# RoboDiscovery-F4_V1_0.net
KiCad netlist of a schematic drawn in EAGLE
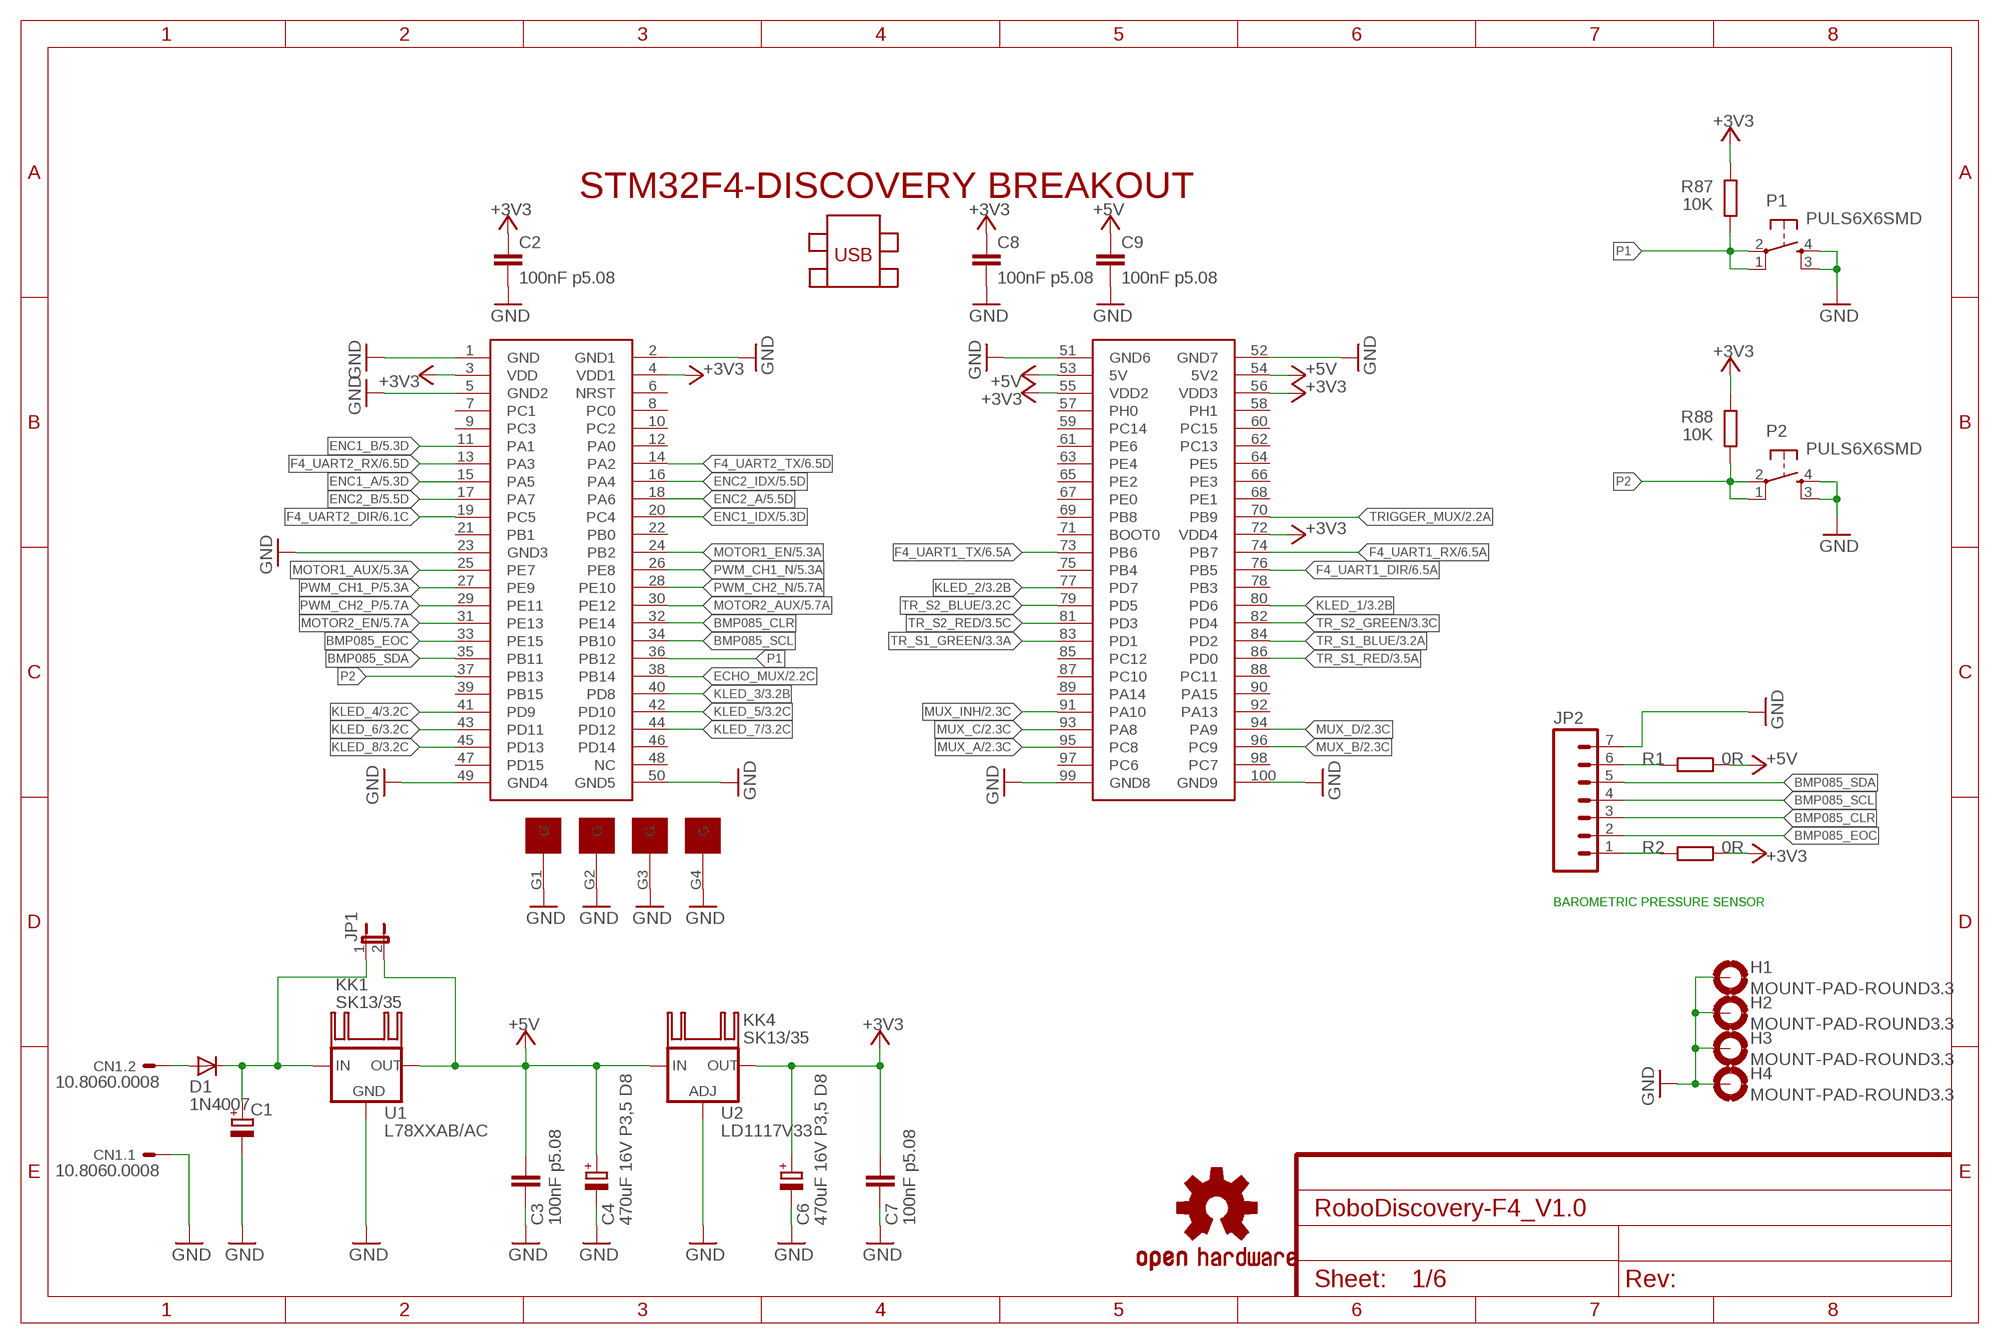
[diagram p0: schematic, sheet 1]
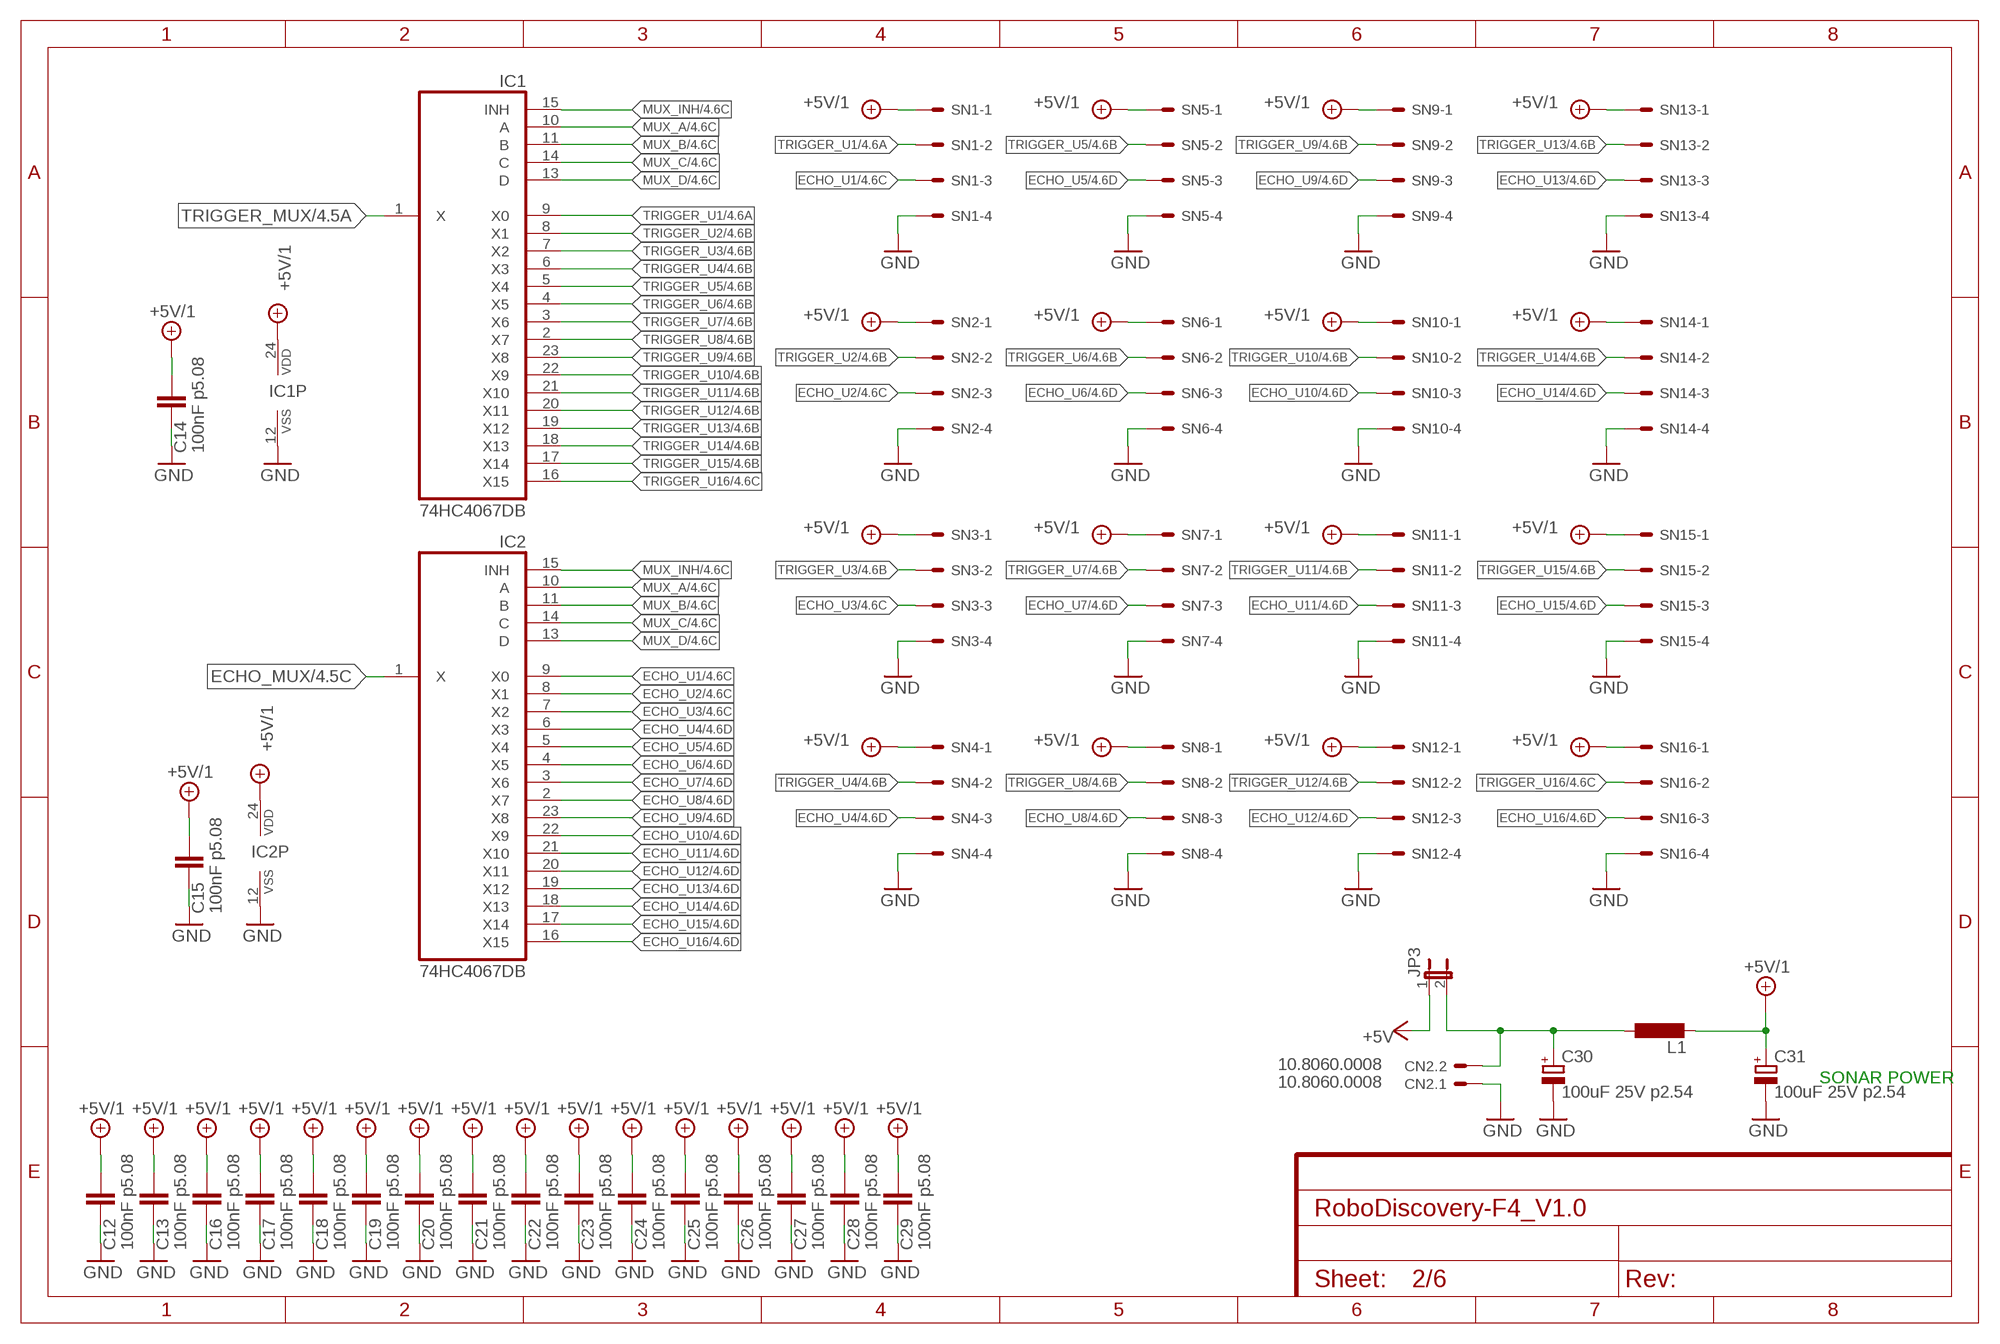
[diagram p1: schematic, sheet 2]
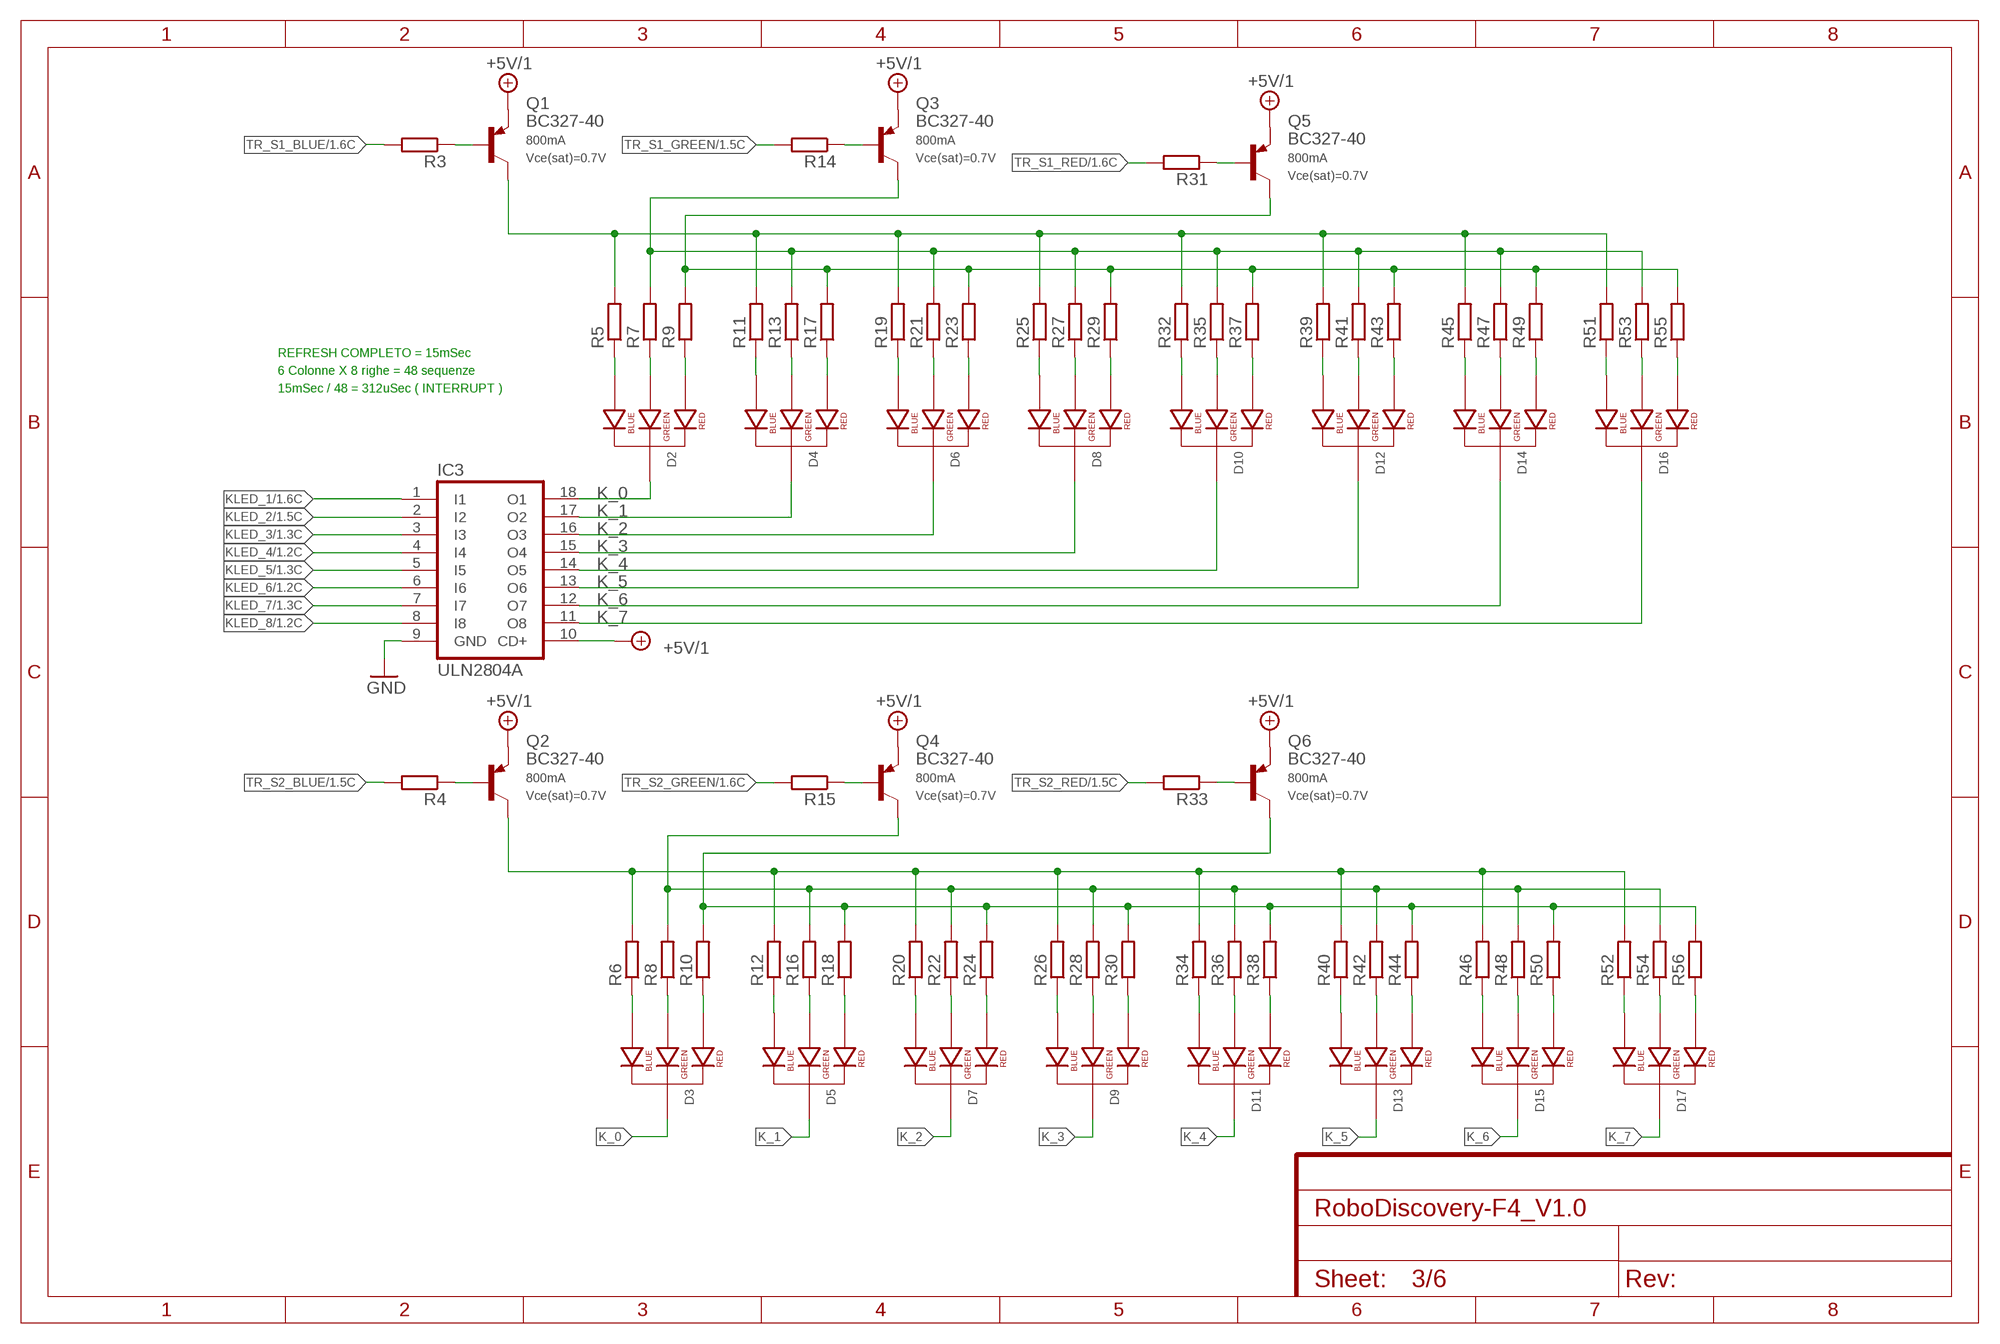
[diagram p2: schematic, sheet 3]
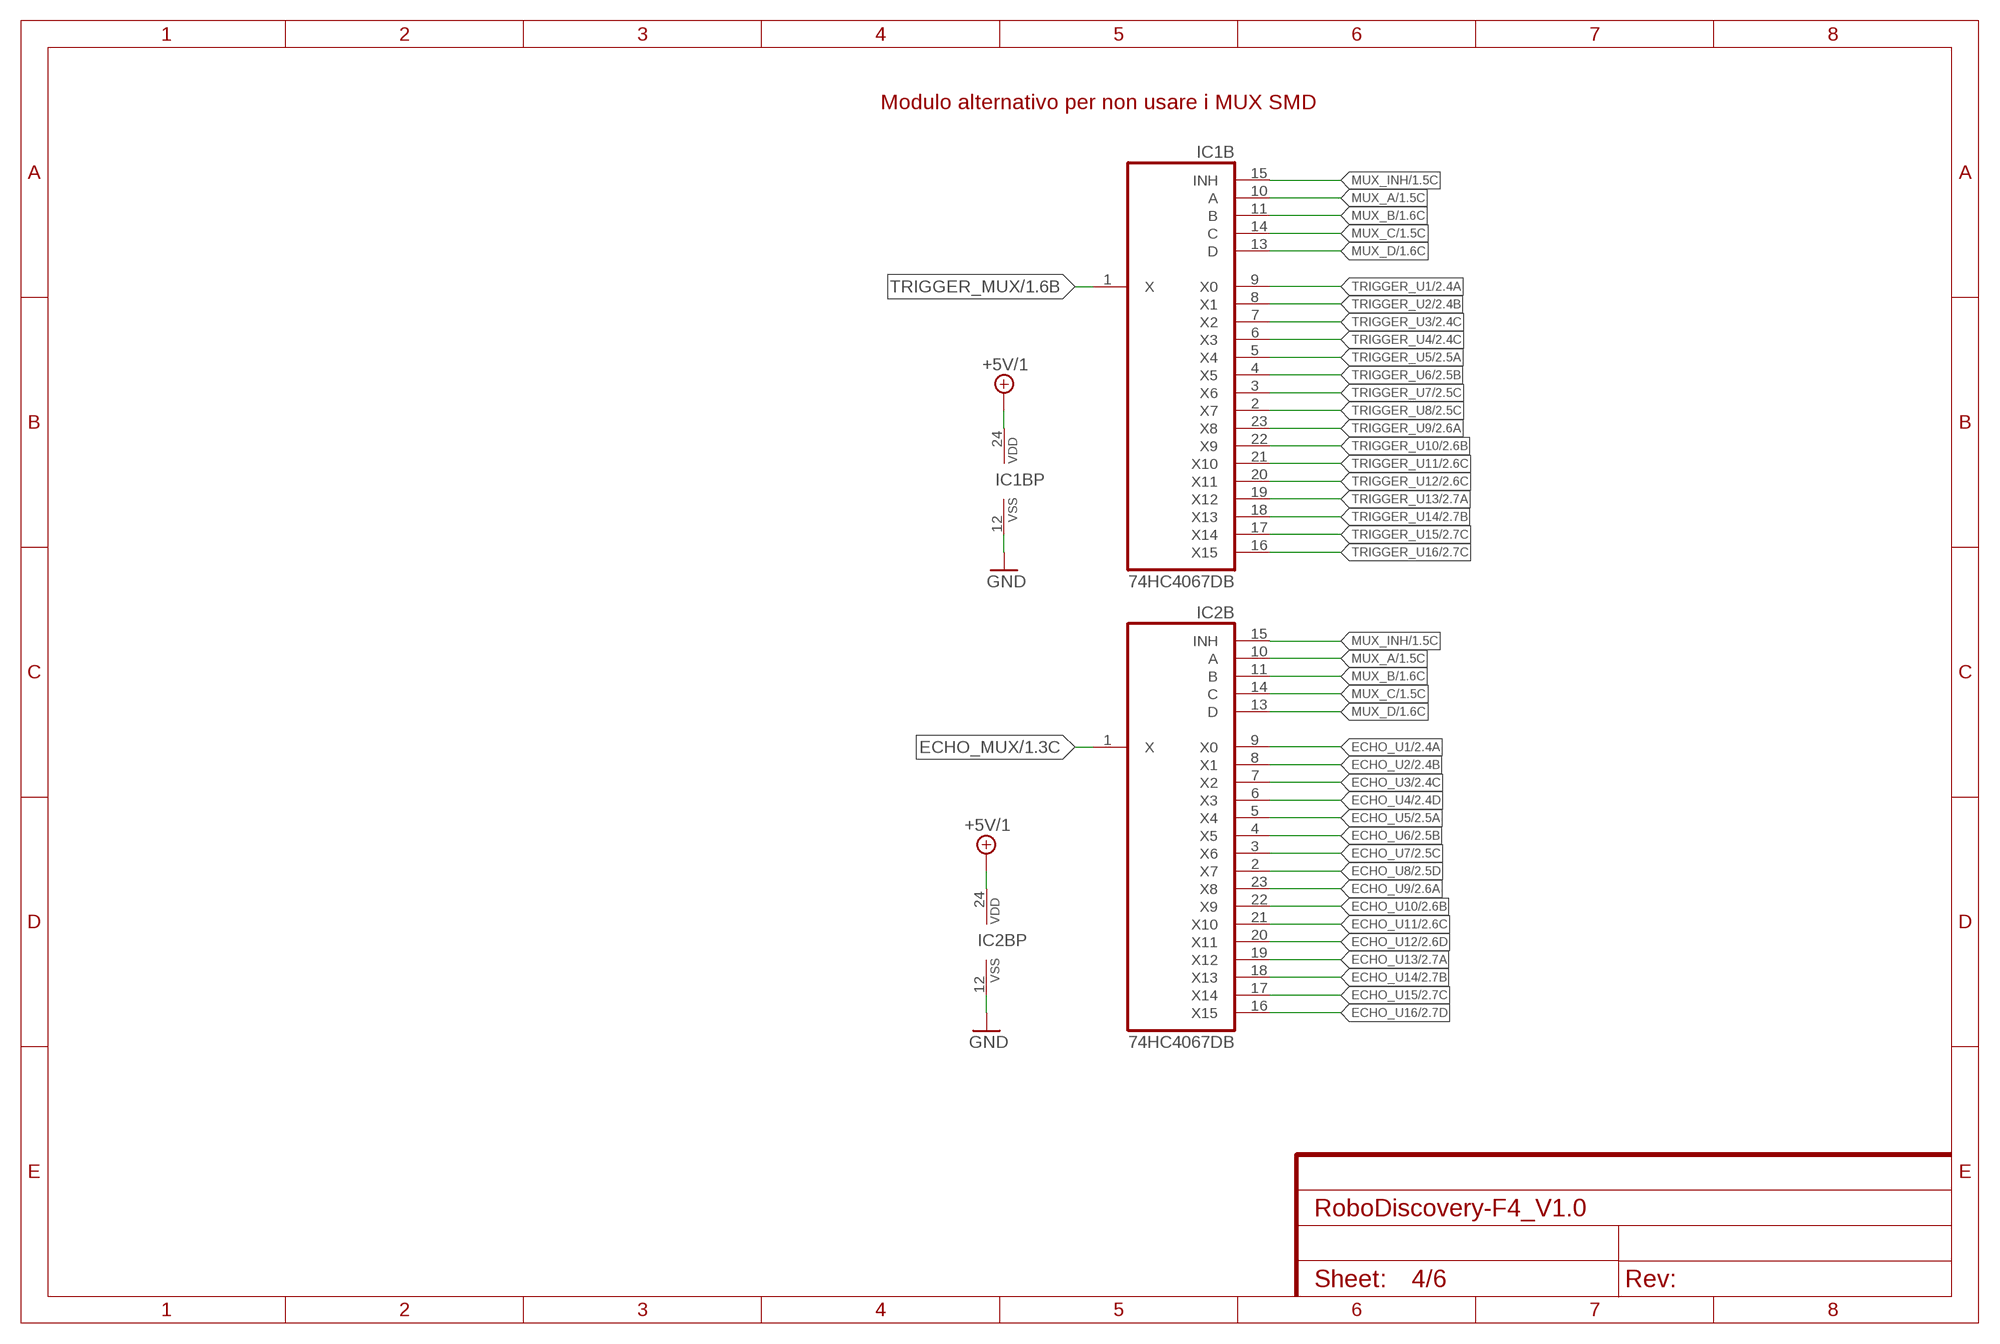
[diagram p3: schematic, sheet 4]
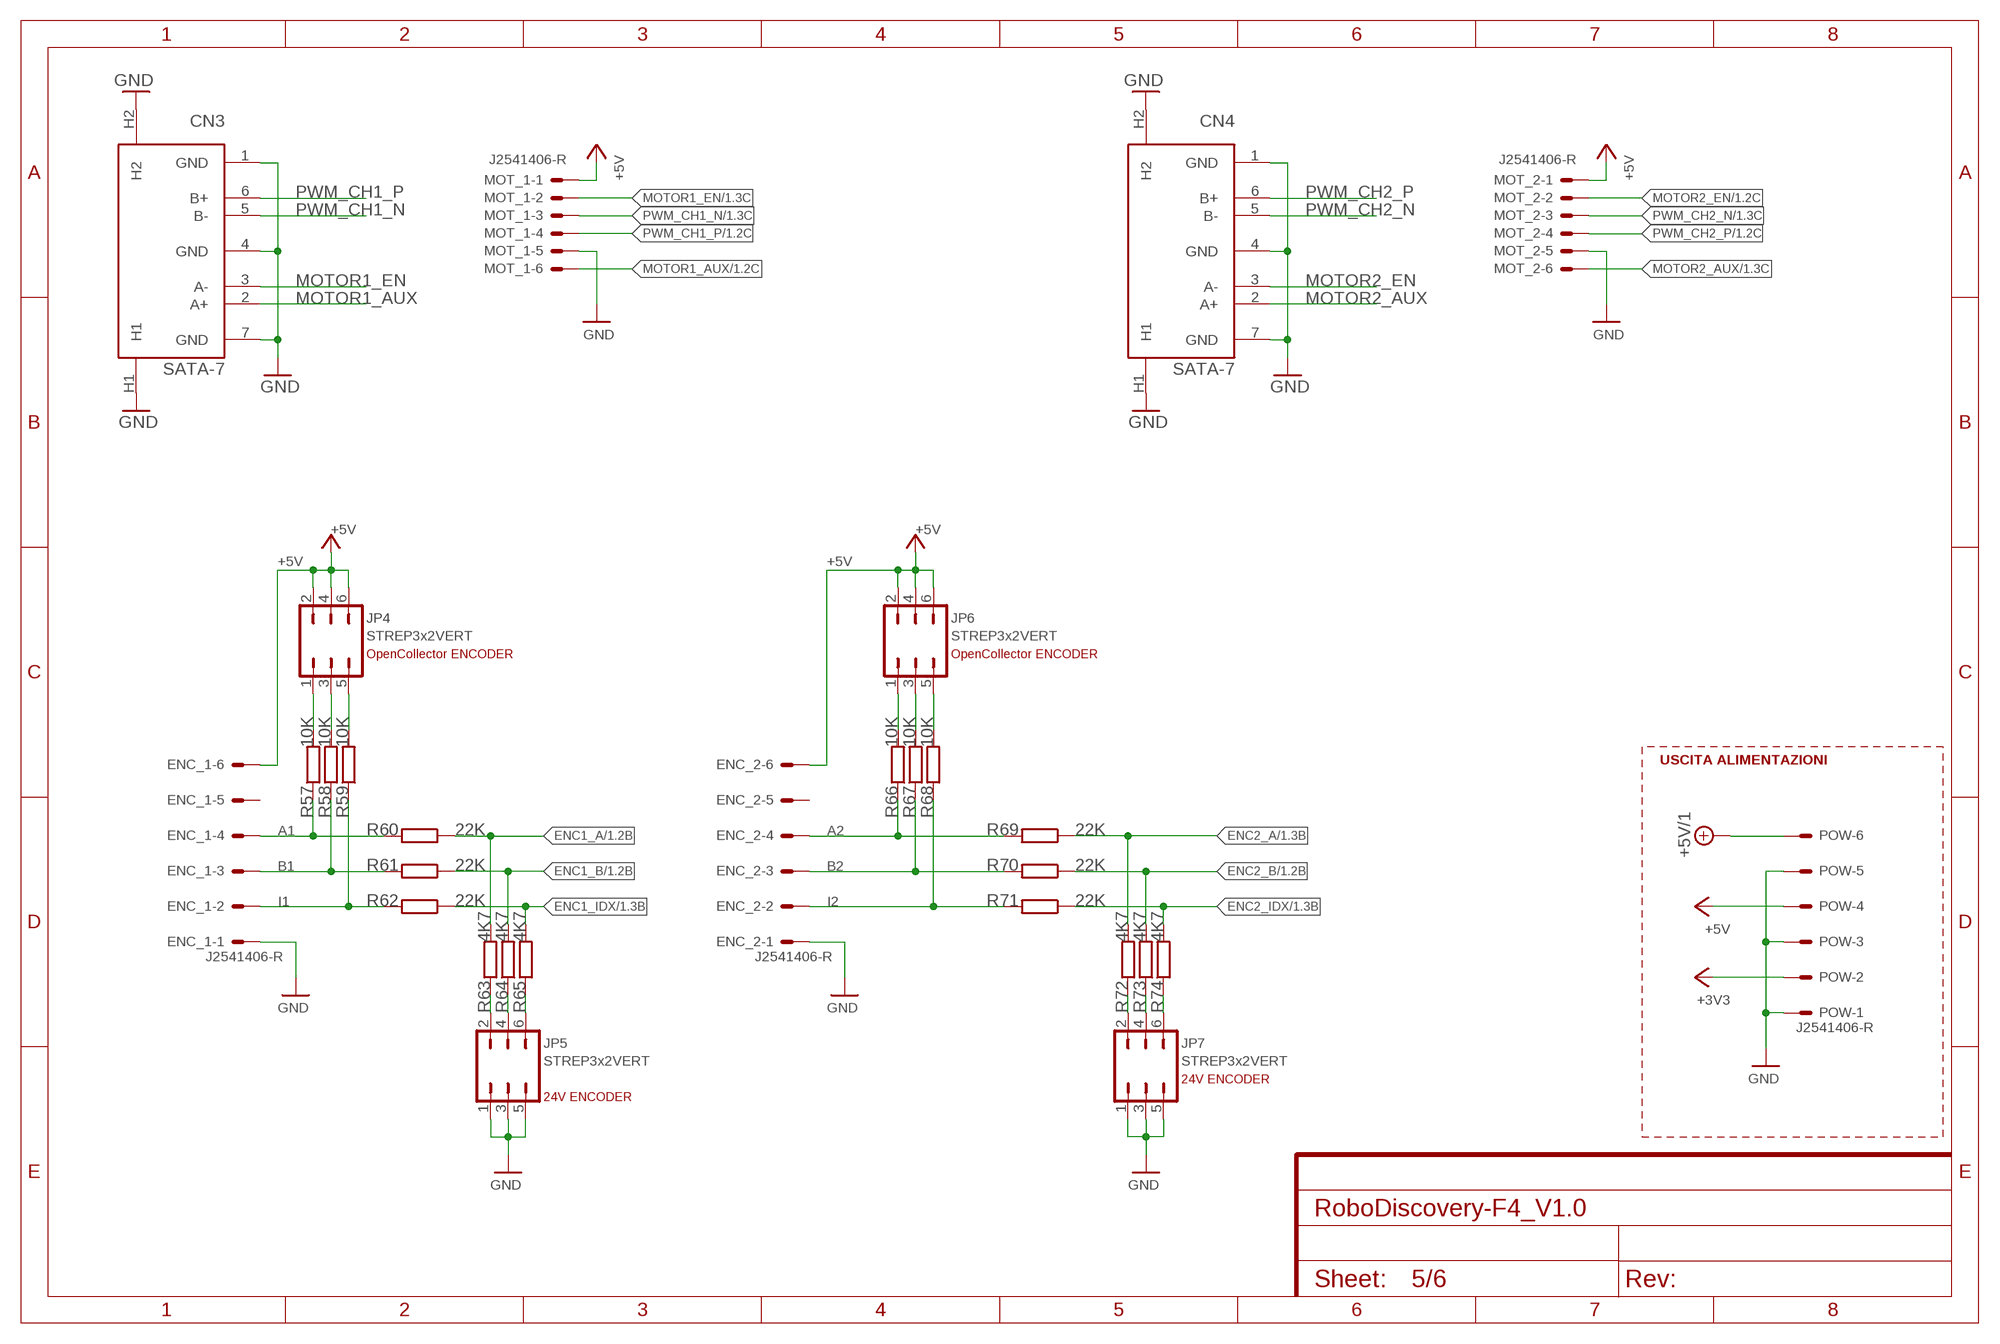
[diagram p4: schematic, sheet 5]
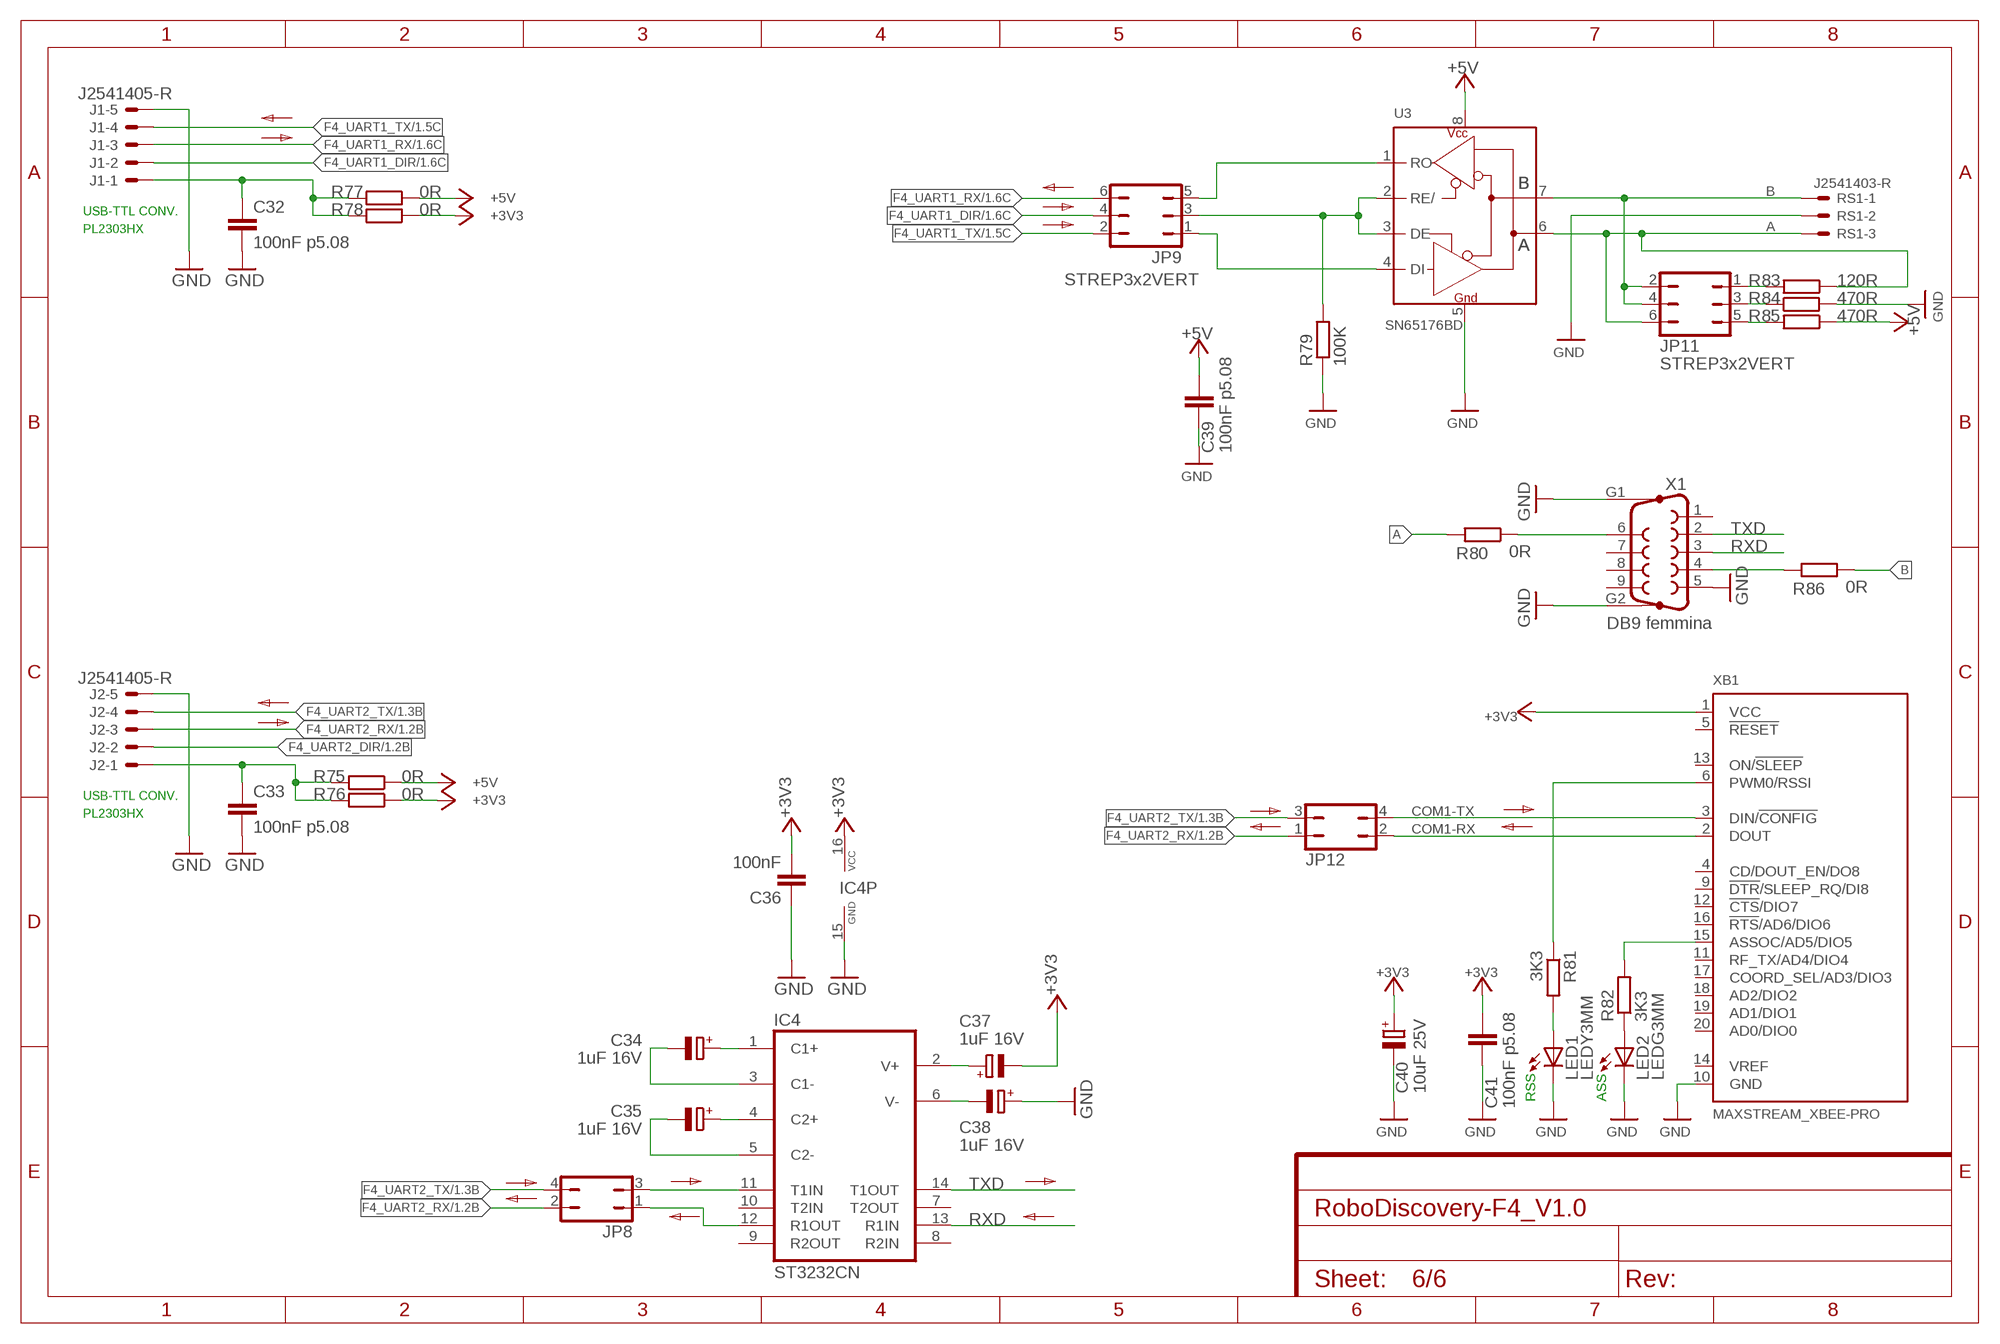
[diagram p5: schematic, sheet 6]

(export (version "E")
  (design (tool "Eeschema 10.0.6"))
  (components
    (comp (ref "D2")
      (value "LED-RGB-CC-THRUDIFFUSE")
      (footprint "eagle-import:LED-RGB-THRU")
      (libsource (lib "eagle-import") (part "LED-RGB-CC-THRUDIFFUSE"))
    )
    (comp (ref "D3")
      (value "LED-RGB-CC-THRUDIFFUSE")
      (footprint "eagle-import:LED-RGB-THRU")
      (libsource (lib "eagle-import") (part "LED-RGB-CC-THRUDIFFUSE"))
    )
    (comp (ref "D4")
      (value "LED-RGB-CC-THRUDIFFUSE")
      (footprint "eagle-import:LED-RGB-THRU")
      (libsource (lib "eagle-import") (part "LED-RGB-CC-THRUDIFFUSE"))
    )
    (comp (ref "D5")
      (value "LED-RGB-CC-THRUDIFFUSE")
      (footprint "eagle-import:LED-RGB-THRU")
      (libsource (lib "eagle-import") (part "LED-RGB-CC-THRUDIFFUSE"))
    )
    (comp (ref "D6")
      (value "LED-RGB-CC-THRUDIFFUSE")
      (footprint "eagle-import:LED-RGB-THRU")
      (libsource (lib "eagle-import") (part "LED-RGB-CC-THRUDIFFUSE"))
    )
    (comp (ref "D7")
      (value "LED-RGB-CC-THRUDIFFUSE")
      (footprint "eagle-import:LED-RGB-THRU")
      (libsource (lib "eagle-import") (part "LED-RGB-CC-THRUDIFFUSE"))
    )
    (comp (ref "D8")
      (value "LED-RGB-CC-THRUDIFFUSE")
      (footprint "eagle-import:LED-RGB-THRU")
      (libsource (lib "eagle-import") (part "LED-RGB-CC-THRUDIFFUSE"))
    )
    (comp (ref "D9")
      (value "LED-RGB-CC-THRUDIFFUSE")
      (footprint "eagle-import:LED-RGB-THRU")
      (libsource (lib "eagle-import") (part "LED-RGB-CC-THRUDIFFUSE"))
    )
    (comp (ref "D10")
      (value "LED-RGB-CC-THRUDIFFUSE")
      (footprint "eagle-import:LED-RGB-THRU")
      (libsource (lib "eagle-import") (part "LED-RGB-CC-THRUDIFFUSE"))
    )
    (comp (ref "D11")
      (value "LED-RGB-CC-THRUDIFFUSE")
      (footprint "eagle-import:LED-RGB-THRU")
      (libsource (lib "eagle-import") (part "LED-RGB-CC-THRUDIFFUSE"))
    )
    (comp (ref "D12")
      (value "LED-RGB-CC-THRUDIFFUSE")
      (footprint "eagle-import:LED-RGB-THRU")
      (libsource (lib "eagle-import") (part "LED-RGB-CC-THRUDIFFUSE"))
    )
    (comp (ref "D13")
      (value "LED-RGB-CC-THRUDIFFUSE")
      (footprint "eagle-import:LED-RGB-THRU")
      (libsource (lib "eagle-import") (part "LED-RGB-CC-THRUDIFFUSE"))
    )
    (comp (ref "D14")
      (value "LED-RGB-CC-THRUDIFFUSE")
      (footprint "eagle-import:LED-RGB-THRU")
      (libsource (lib "eagle-import") (part "LED-RGB-CC-THRUDIFFUSE"))
    )
    (comp (ref "D15")
      (value "LED-RGB-CC-THRUDIFFUSE")
      (footprint "eagle-import:LED-RGB-THRU")
      (libsource (lib "eagle-import") (part "LED-RGB-CC-THRUDIFFUSE"))
    )
    (comp (ref "D16")
      (value "LED-RGB-CC-THRUDIFFUSE")
      (footprint "eagle-import:LED-RGB-THRU")
      (libsource (lib "eagle-import") (part "LED-RGB-CC-THRUDIFFUSE"))
    )
    (comp (ref "D17")
      (value "LED-RGB-CC-THRUDIFFUSE")
      (footprint "eagle-import:LED-RGB-THRU")
      (libsource (lib "eagle-import") (part "LED-RGB-CC-THRUDIFFUSE"))
    )
    (comp (ref "IC3")
      (value "ULN2804A")
      (footprint "eagle-import:DIL18")
      (libsource (lib "eagle-import") (part "ULN2804A"))
    )
    (comp (ref "Q1")
      (value "BC327-40")
      (footprint "eagle-import:TO92-EBC")
      (fields (field (name "I") "800mA") (field (name "VCESAT") "Vce(sat)=0.7V"))
      (libsource (lib "eagle-import") (part "BC327-40"))
    )
    (comp (ref "Q2")
      (value "BC327-40")
      (footprint "eagle-import:TO92-EBC")
      (fields (field (name "I") "800mA") (field (name "VCESAT") "Vce(sat)=0.7V"))
      (libsource (lib "eagle-import") (part "BC327-40"))
    )
    (comp (ref "Q3")
      (value "BC327-40")
      (footprint "eagle-import:TO92-EBC")
      (fields (field (name "I") "800mA") (field (name "VCESAT") "Vce(sat)=0.7V"))
      (libsource (lib "eagle-import") (part "BC327-40"))
    )
    (comp (ref "Q4")
      (value "BC327-40")
      (footprint "eagle-import:TO92-EBC")
      (fields (field (name "I") "800mA") (field (name "VCESAT") "Vce(sat)=0.7V"))
      (libsource (lib "eagle-import") (part "BC327-40"))
    )
    (comp (ref "Q5")
      (value "BC327-40")
      (footprint "eagle-import:TO92-EBC")
      (fields (field (name "I") "800mA") (field (name "VCESAT") "Vce(sat)=0.7V"))
      (libsource (lib "eagle-import") (part "BC327-40"))
    )
    (comp (ref "Q6")
      (value "BC327-40")
      (footprint "eagle-import:TO92-EBC")
      (fields (field (name "I") "800mA") (field (name "VCESAT") "Vce(sat)=0.7V"))
      (libsource (lib "eagle-import") (part "BC327-40"))
    )
    (comp (ref "R3")
      (value "R-EU_0207/7")
      (footprint "eagle-import:0207_7")
      (libsource (lib "eagle-import") (part "R-EU_0207/7"))
    )
    (comp (ref "R4")
      (value "R-EU_0207/7")
      (footprint "eagle-import:0207_7")
      (libsource (lib "eagle-import") (part "R-EU_0207/7"))
    )
    (comp (ref "R5")
      (value "R-EU_0207/7")
      (footprint "eagle-import:0207_7")
      (libsource (lib "eagle-import") (part "R-EU_0207/7"))
    )
    (comp (ref "R6")
      (value "R-EU_0207/7")
      (footprint "eagle-import:0207_7")
      (libsource (lib "eagle-import") (part "R-EU_0207/7"))
    )
    (comp (ref "R7")
      (value "R-EU_0207/7")
      (footprint "eagle-import:0207_7")
      (libsource (lib "eagle-import") (part "R-EU_0207/7"))
    )
    (comp (ref "R8")
      (value "R-EU_0207/7")
      (footprint "eagle-import:0207_7")
      (libsource (lib "eagle-import") (part "R-EU_0207/7"))
    )
    (comp (ref "R9")
      (value "R-EU_0207/7")
      (footprint "eagle-import:0207_7")
      (libsource (lib "eagle-import") (part "R-EU_0207/7"))
    )
    (comp (ref "R10")
      (value "R-EU_0207/7")
      (footprint "eagle-import:0207_7")
      (libsource (lib "eagle-import") (part "R-EU_0207/7"))
    )
    (comp (ref "R11")
      (value "R-EU_0207/7")
      (footprint "eagle-import:0207_7")
      (libsource (lib "eagle-import") (part "R-EU_0207/7"))
    )
    (comp (ref "R12")
      (value "R-EU_0207/7")
      (footprint "eagle-import:0207_7")
      (libsource (lib "eagle-import") (part "R-EU_0207/7"))
    )
    (comp (ref "R13")
      (value "R-EU_0207/7")
      (footprint "eagle-import:0207_7")
      (libsource (lib "eagle-import") (part "R-EU_0207/7"))
    )
    (comp (ref "R14")
      (value "R-EU_0207/7")
      (footprint "eagle-import:0207_7")
      (libsource (lib "eagle-import") (part "R-EU_0207/7"))
    )
    (comp (ref "R15")
      (value "R-EU_0207/7")
      (footprint "eagle-import:0207_7")
      (libsource (lib "eagle-import") (part "R-EU_0207/7"))
    )
    (comp (ref "R16")
      (value "R-EU_0207/7")
      (footprint "eagle-import:0207_7")
      (libsource (lib "eagle-import") (part "R-EU_0207/7"))
    )
    (comp (ref "R17")
      (value "R-EU_0207/7")
      (footprint "eagle-import:0207_7")
      (libsource (lib "eagle-import") (part "R-EU_0207/7"))
    )
    (comp (ref "R18")
      (value "R-EU_0207/7")
      (footprint "eagle-import:0207_7")
      (libsource (lib "eagle-import") (part "R-EU_0207/7"))
    )
    (comp (ref "R19")
      (value "R-EU_0207/7")
      (footprint "eagle-import:0207_7")
      (libsource (lib "eagle-import") (part "R-EU_0207/7"))
    )
    (comp (ref "R20")
      (value "R-EU_0207/7")
      (footprint "eagle-import:0207_7")
      (libsource (lib "eagle-import") (part "R-EU_0207/7"))
    )
    (comp (ref "R21")
      (value "R-EU_0207/7")
      (footprint "eagle-import:0207_7")
      (libsource (lib "eagle-import") (part "R-EU_0207/7"))
    )
    (comp (ref "R22")
      (value "R-EU_0207/7")
      (footprint "eagle-import:0207_7")
      (libsource (lib "eagle-import") (part "R-EU_0207/7"))
    )
    (comp (ref "R23")
      (value "R-EU_0207/7")
      (footprint "eagle-import:0207_7")
      (libsource (lib "eagle-import") (part "R-EU_0207/7"))
    )
    (comp (ref "R24")
      (value "R-EU_0207/7")
      (footprint "eagle-import:0207_7")
      (libsource (lib "eagle-import") (part "R-EU_0207/7"))
    )
    (comp (ref "R25")
      (value "R-EU_0207/7")
      (footprint "eagle-import:0207_7")
      (libsource (lib "eagle-import") (part "R-EU_0207/7"))
    )
    (comp (ref "R26")
      (value "R-EU_0207/7")
      (footprint "eagle-import:0207_7")
      (libsource (lib "eagle-import") (part "R-EU_0207/7"))
    )
    (comp (ref "R27")
      (value "R-EU_0207/7")
      (footprint "eagle-import:0207_7")
      (libsource (lib "eagle-import") (part "R-EU_0207/7"))
    )
    (comp (ref "R28")
      (value "R-EU_0207/7")
      (footprint "eagle-import:0207_7")
      (libsource (lib "eagle-import") (part "R-EU_0207/7"))
    )
    (comp (ref "R29")
      (value "R-EU_0207/7")
      (footprint "eagle-import:0207_7")
      (libsource (lib "eagle-import") (part "R-EU_0207/7"))
    )
    (comp (ref "R30")
      (value "R-EU_0207/7")
      (footprint "eagle-import:0207_7")
      (libsource (lib "eagle-import") (part "R-EU_0207/7"))
    )
    (comp (ref "R31")
      (value "R-EU_0207/7")
      (footprint "eagle-import:0207_7")
      (libsource (lib "eagle-import") (part "R-EU_0207/7"))
    )
    (comp (ref "R32")
      (value "R-EU_0207/7")
      (footprint "eagle-import:0207_7")
      (libsource (lib "eagle-import") (part "R-EU_0207/7"))
    )
    (comp (ref "R33")
      (value "R-EU_0207/7")
      (footprint "eagle-import:0207_7")
      (libsource (lib "eagle-import") (part "R-EU_0207/7"))
    )
    (comp (ref "R34")
      (value "R-EU_0207/7")
      (footprint "eagle-import:0207_7")
      (libsource (lib "eagle-import") (part "R-EU_0207/7"))
    )
    (comp (ref "R35")
      (value "R-EU_0207/7")
      (footprint "eagle-import:0207_7")
      (libsource (lib "eagle-import") (part "R-EU_0207/7"))
    )
    (comp (ref "R36")
      (value "R-EU_0207/7")
      (footprint "eagle-import:0207_7")
      (libsource (lib "eagle-import") (part "R-EU_0207/7"))
    )
    (comp (ref "R37")
      (value "R-EU_0207/7")
      (footprint "eagle-import:0207_7")
      (libsource (lib "eagle-import") (part "R-EU_0207/7"))
    )
    (comp (ref "R38")
      (value "R-EU_0207/7")
      (footprint "eagle-import:0207_7")
      (libsource (lib "eagle-import") (part "R-EU_0207/7"))
    )
    (comp (ref "R39")
      (value "R-EU_0207/7")
      (footprint "eagle-import:0207_7")
      (libsource (lib "eagle-import") (part "R-EU_0207/7"))
    )
    (comp (ref "R40")
      (value "R-EU_0207/7")
      (footprint "eagle-import:0207_7")
      (libsource (lib "eagle-import") (part "R-EU_0207/7"))
    )
    (comp (ref "R41")
      (value "R-EU_0207/7")
      (footprint "eagle-import:0207_7")
      (libsource (lib "eagle-import") (part "R-EU_0207/7"))
    )
    (comp (ref "R42")
      (value "R-EU_0207/7")
      (footprint "eagle-import:0207_7")
      (libsource (lib "eagle-import") (part "R-EU_0207/7"))
    )
    (comp (ref "R43")
      (value "R-EU_0207/7")
      (footprint "eagle-import:0207_7")
      (libsource (lib "eagle-import") (part "R-EU_0207/7"))
    )
    (comp (ref "R44")
      (value "R-EU_0207/7")
      (footprint "eagle-import:0207_7")
      (libsource (lib "eagle-import") (part "R-EU_0207/7"))
    )
    (comp (ref "R45")
      (value "R-EU_0207/7")
      (footprint "eagle-import:0207_7")
      (libsource (lib "eagle-import") (part "R-EU_0207/7"))
    )
    (comp (ref "R46")
      (value "R-EU_0207/7")
      (footprint "eagle-import:0207_7")
      (libsource (lib "eagle-import") (part "R-EU_0207/7"))
    )
    (comp (ref "R47")
      (value "R-EU_0207/7")
      (footprint "eagle-import:0207_7")
      (libsource (lib "eagle-import") (part "R-EU_0207/7"))
    )
    (comp (ref "R48")
      (value "R-EU_0207/7")
      (footprint "eagle-import:0207_7")
      (libsource (lib "eagle-import") (part "R-EU_0207/7"))
    )
    (comp (ref "R49")
      (value "R-EU_0207/7")
      (footprint "eagle-import:0207_7")
      (libsource (lib "eagle-import") (part "R-EU_0207/7"))
    )
    (comp (ref "R50")
      (value "R-EU_0207/7")
      (footprint "eagle-import:0207_7")
      (libsource (lib "eagle-import") (part "R-EU_0207/7"))
    )
    (comp (ref "R51")
      (value "R-EU_0207/7")
      (footprint "eagle-import:0207_7")
      (libsource (lib "eagle-import") (part "R-EU_0207/7"))
    )
    (comp (ref "R52")
      (value "R-EU_0207/7")
      (footprint "eagle-import:0207_7")
      (libsource (lib "eagle-import") (part "R-EU_0207/7"))
    )
    (comp (ref "R53")
      (value "R-EU_0207/7")
      (footprint "eagle-import:0207_7")
      (libsource (lib "eagle-import") (part "R-EU_0207/7"))
    )
    (comp (ref "R54")
      (value "R-EU_0207/7")
      (footprint "eagle-import:0207_7")
      (libsource (lib "eagle-import") (part "R-EU_0207/7"))
    )
    (comp (ref "R55")
      (value "R-EU_0207/7")
      (footprint "eagle-import:0207_7")
      (libsource (lib "eagle-import") (part "R-EU_0207/7"))
    )
    (comp (ref "R56")
      (value "R-EU_0207/7")
      (footprint "eagle-import:0207_7")
      (libsource (lib "eagle-import") (part "R-EU_0207/7"))
    )
    (comp (ref "C12")
      (value "100nF p5.08")
      (footprint "eagle-import:C050-024X044")
      (libsource (lib "eagle-import") (part "C-EU050-024X044"))
    )
    (comp (ref "C13")
      (value "100nF p5.08")
      (footprint "eagle-import:C050-024X044")
      (libsource (lib "eagle-import") (part "C-EU050-024X044"))
    )
    (comp (ref "C14")
      (value "100nF p5.08")
      (footprint "eagle-import:C050-024X044")
      (libsource (lib "eagle-import") (part "C-EU050-024X044"))
    )
    (comp (ref "C15")
      (value "100nF p5.08")
      (footprint "eagle-import:C050-024X044")
      (libsource (lib "eagle-import") (part "C-EU050-024X044"))
    )
    (comp (ref "C16")
      (value "100nF p5.08")
      (footprint "eagle-import:C050-024X044")
      (libsource (lib "eagle-import") (part "C-EU050-024X044"))
    )
    (comp (ref "C17")
      (value "100nF p5.08")
      (footprint "eagle-import:C050-024X044")
      (libsource (lib "eagle-import") (part "C-EU050-024X044"))
    )
    (comp (ref "C18")
      (value "100nF p5.08")
      (footprint "eagle-import:C050-024X044")
      (libsource (lib "eagle-import") (part "C-EU050-024X044"))
    )
    (comp (ref "C19")
      (value "100nF p5.08")
      (footprint "eagle-import:C050-024X044")
      (libsource (lib "eagle-import") (part "C-EU050-024X044"))
    )
    (comp (ref "C20")
      (value "100nF p5.08")
      (footprint "eagle-import:C050-024X044")
      (libsource (lib "eagle-import") (part "C-EU050-024X044"))
    )
    (comp (ref "C21")
      (value "100nF p5.08")
      (footprint "eagle-import:C050-024X044")
      (libsource (lib "eagle-import") (part "C-EU050-024X044"))
    )
    (comp (ref "C22")
      (value "100nF p5.08")
      (footprint "eagle-import:C050-024X044")
      (libsource (lib "eagle-import") (part "C-EU050-024X044"))
    )
    (comp (ref "C23")
      (value "100nF p5.08")
      (footprint "eagle-import:C050-024X044")
      (libsource (lib "eagle-import") (part "C-EU050-024X044"))
    )
    (comp (ref "C24")
      (value "100nF p5.08")
      (footprint "eagle-import:C050-024X044")
      (libsource (lib "eagle-import") (part "C-EU050-024X044"))
    )
    (comp (ref "C25")
      (value "100nF p5.08")
      (footprint "eagle-import:C050-024X044")
      (libsource (lib "eagle-import") (part "C-EU050-024X044"))
    )
    (comp (ref "C26")
      (value "100nF p5.08")
      (footprint "eagle-import:C050-024X044")
      (libsource (lib "eagle-import") (part "C-EU050-024X044"))
    )
    (comp (ref "C27")
      (value "100nF p5.08")
      (footprint "eagle-import:C050-024X044")
      (libsource (lib "eagle-import") (part "C-EU050-024X044"))
    )
    (comp (ref "C28")
      (value "100nF p5.08")
      (footprint "eagle-import:C050-024X044")
      (libsource (lib "eagle-import") (part "C-EU050-024X044"))
    )
    (comp (ref "C29")
      (value "100nF p5.08")
      (footprint "eagle-import:C050-024X044")
      (libsource (lib "eagle-import") (part "C-EU050-024X044"))
    )
    (comp (ref "C30")
      (value "100uF 25V p2.54")
      (footprint "eagle-import:E2,5-6")
      (libsource (lib "eagle-import") (part "CPOL-EUE2.5-6"))
    )
    (comp (ref "C31")
      (value "100uF 25V p2.54")
      (footprint "eagle-import:E2,5-6")
      (libsource (lib "eagle-import") (part "CPOL-EUE2.5-6"))
    )
    (comp (ref "CN2")
      (value "10.8060.0008")
      (footprint "eagle-import:300-021-13_2P_5VE")
      (libsource (lib "eagle-import") (part "10.8060.0008"))
    )
    (comp (ref "IC1")
      (value "74HC4067DB")
      (footprint "eagle-import:SO24W")
      (libsource (lib "eagle-import") (part "4067D"))
    )
    (comp (ref "IC2")
      (value "74HC4067DB")
      (footprint "eagle-import:SO24W")
      (libsource (lib "eagle-import") (part "4067D"))
    )
    (comp (ref "JP3")
      (value "JP1E")
      (footprint "eagle-import:JP1")
      (libsource (lib "eagle-import") (part "JP1E"))
    )
    (comp (ref "L1")
      (value "L-EU2200-12.7")
      (footprint "eagle-import:2200-12.7")
      (libsource (lib "eagle-import") (part "L-EU2200-12.7"))
    )
    (comp (ref "SN1")
      (value "22-27-2041-04")
      (footprint "eagle-import:6410-04")
      (libsource (lib "eagle-import") (part "22-?-0427-2041"))
    )
    (comp (ref "SN2")
      (value "22-27-2041-04")
      (footprint "eagle-import:6410-04")
      (libsource (lib "eagle-import") (part "22-?-0427-2041"))
    )
    (comp (ref "SN3")
      (value "22-27-2041-04")
      (footprint "eagle-import:6410-04")
      (libsource (lib "eagle-import") (part "22-?-0427-2041"))
    )
    (comp (ref "SN4")
      (value "22-27-2041-04")
      (footprint "eagle-import:6410-04")
      (libsource (lib "eagle-import") (part "22-?-0427-2041"))
    )
    (comp (ref "SN5")
      (value "22-27-2041-04")
      (footprint "eagle-import:6410-04")
      (libsource (lib "eagle-import") (part "22-?-0427-2041"))
    )
    (comp (ref "SN6")
      (value "22-27-2041-04")
      (footprint "eagle-import:6410-04")
      (libsource (lib "eagle-import") (part "22-?-0427-2041"))
    )
    (comp (ref "SN7")
      (value "22-27-2041-04")
      (footprint "eagle-import:6410-04")
      (libsource (lib "eagle-import") (part "22-?-0427-2041"))
    )
    (comp (ref "SN8")
      (value "22-27-2041-04")
      (footprint "eagle-import:6410-04")
      (libsource (lib "eagle-import") (part "22-?-0427-2041"))
    )
    (comp (ref "SN9")
      (value "22-27-2041-04")
      (footprint "eagle-import:6410-04")
      (libsource (lib "eagle-import") (part "22-?-0427-2041"))
    )
    (comp (ref "SN10")
      (value "22-27-2041-04")
      (footprint "eagle-import:6410-04")
      (libsource (lib "eagle-import") (part "22-?-0427-2041"))
    )
    (comp (ref "SN11")
      (value "22-27-2041-04")
      (footprint "eagle-import:6410-04")
      (libsource (lib "eagle-import") (part "22-?-0427-2041"))
    )
    (comp (ref "SN12")
      (value "22-27-2041-04")
      (footprint "eagle-import:6410-04")
      (libsource (lib "eagle-import") (part "22-?-0427-2041"))
    )
    (comp (ref "SN13")
      (value "22-27-2041-04")
      (footprint "eagle-import:6410-04")
      (libsource (lib "eagle-import") (part "22-?-0427-2041"))
    )
    (comp (ref "SN14")
      (value "22-27-2041-04")
      (footprint "eagle-import:6410-04")
      (libsource (lib "eagle-import") (part "22-?-0427-2041"))
    )
    (comp (ref "SN15")
      (value "22-27-2041-04")
      (footprint "eagle-import:6410-04")
      (libsource (lib "eagle-import") (part "22-?-0427-2041"))
    )
    (comp (ref "SN16")
      (value "22-27-2041-04")
      (footprint "eagle-import:6410-04")
      (libsource (lib "eagle-import") (part "22-?-0427-2041"))
    )
    (comp (ref "C32")
      (value "100nF p5.08")
      (footprint "eagle-import:C050-024X044")
      (libsource (lib "eagle-import") (part "C-EU050-024X044"))
    )
    (comp (ref "C33")
      (value "100nF p5.08")
      (footprint "eagle-import:C050-024X044")
      (libsource (lib "eagle-import") (part "C-EU050-024X044"))
    )
    (comp (ref "C34")
      (value "1uF 16V")
      (footprint "eagle-import:E2,5-5")
      (libsource (lib "eagle-import") (part "CPOL-EUE2.5-5"))
    )
    (comp (ref "C35")
      (value "1uF 16V")
      (footprint "eagle-import:E2,5-5")
      (libsource (lib "eagle-import") (part "CPOL-EUE2.5-5"))
    )
    (comp (ref "C36")
      (value "100nF")
      (footprint "eagle-import:C025-025X050")
      (libsource (lib "eagle-import") (part "C-EU025-025X050"))
    )
    (comp (ref "C37")
      (value "1uF 16V")
      (footprint "eagle-import:E2,5-5")
      (libsource (lib "eagle-import") (part "CPOL-EUE2.5-5"))
    )
    (comp (ref "C38")
      (value "1uF 16V")
      (footprint "eagle-import:E2,5-5")
      (libsource (lib "eagle-import") (part "CPOL-EUE2.5-5"))
    )
    (comp (ref "C39")
      (value "100nF p5.08")
      (footprint "eagle-import:C050-024X044")
      (libsource (lib "eagle-import") (part "C-EU050-024X044"))
    )
    (comp (ref "C40")
      (value "10uF 25V")
      (footprint "eagle-import:E2,5-5")
      (libsource (lib "eagle-import") (part "CPOL-EUE2.5-5"))
    )
    (comp (ref "C41")
      (value "100nF p5.08")
      (footprint "eagle-import:C050-024X044")
      (libsource (lib "eagle-import") (part "C-EU050-024X044"))
    )
    (comp (ref "IC4")
      (value "ST3232CN")
      (footprint "eagle-import:DIL16")
      (fields (field (name "MF") "MAXIM") (field (name "MPN") "MAX232ACPE+"))
      (libsource (lib "eagle-import") (part "MAX232"))
    )
    (comp (ref "J1")
      (value "J2541405-R")
      (footprint "eagle-import:6410-05")
      (libsource (lib "eagle-import") (part "22-?-0527-2051"))
    )
    (comp (ref "J2")
      (value "J2541405-R")
      (footprint "eagle-import:6410-05")
      (libsource (lib "eagle-import") (part "22-?-0527-2051"))
    )
    (comp (ref "JP8")
      (value "JP2Q")
      (footprint "eagle-import:JP2Q")
      (libsource (lib "eagle-import") (part "JP2Q"))
    )
    (comp (ref "JP9")
      (value "STREP3x2VERT")
      (footprint "eagle-import:JP3Q")
      (libsource (lib "eagle-import") (part "JP3Q"))
    )
    (comp (ref "JP11")
      (value "STREP3x2VERT")
      (footprint "eagle-import:JP3Q")
      (libsource (lib "eagle-import") (part "JP3Q"))
    )
    (comp (ref "JP12")
      (value "JP2Q")
      (footprint "eagle-import:JP2Q")
      (libsource (lib "eagle-import") (part "JP2Q"))
    )
    (comp (ref "LED1")
      (value "LEDY3MM")
      (footprint "eagle-import:LED3MM")
      (libsource (lib "eagle-import") (part "LED3MM"))
    )
    (comp (ref "LED2")
      (value "LEDG3MM")
      (footprint "eagle-import:LED3MM")
      (libsource (lib "eagle-import") (part "LED3MM"))
    )
    (comp (ref "R75")
      (value "0R")
      (footprint "eagle-import:0207_7")
      (libsource (lib "eagle-import") (part "R-EU_0207/7"))
    )
    (comp (ref "R76")
      (value "0R")
      (footprint "eagle-import:0207_7")
      (libsource (lib "eagle-import") (part "R-EU_0207/7"))
    )
    (comp (ref "R77")
      (value "0R")
      (footprint "eagle-import:0207_7")
      (libsource (lib "eagle-import") (part "R-EU_0207/7"))
    )
    (comp (ref "R78")
      (value "0R")
      (footprint "eagle-import:0207_7")
      (libsource (lib "eagle-import") (part "R-EU_0207/7"))
    )
    (comp (ref "R79")
      (value "100K")
      (footprint "eagle-import:0207_7")
      (libsource (lib "eagle-import") (part "R-EU_0207/7"))
    )
    (comp (ref "R80")
      (value "0R")
      (footprint "eagle-import:0207_7")
      (libsource (lib "eagle-import") (part "R-EU_0207/7"))
    )
    (comp (ref "R81")
      (value "3K3")
      (footprint "eagle-import:0207_7")
      (libsource (lib "eagle-import") (part "R-EU_0207/7"))
    )
    (comp (ref "R82")
      (value "3K3")
      (footprint "eagle-import:0207_7")
      (libsource (lib "eagle-import") (part "R-EU_0207/7"))
    )
    (comp (ref "R83")
      (value "120R")
      (footprint "eagle-import:0207_7")
      (libsource (lib "eagle-import") (part "R-EU_0207/7"))
    )
    (comp (ref "R84")
      (value "470R")
      (footprint "eagle-import:0207_7")
      (libsource (lib "eagle-import") (part "R-EU_0207/7"))
    )
    (comp (ref "R85")
      (value "470R")
      (footprint "eagle-import:0207_7")
      (libsource (lib "eagle-import") (part "R-EU_0207/7"))
    )
    (comp (ref "R86")
      (value "0R")
      (footprint "eagle-import:0207_7")
      (libsource (lib "eagle-import") (part "R-EU_0207/7"))
    )
    (comp (ref "RS1")
      (value "J2541403-R")
      (footprint "eagle-import:6410-03")
      (libsource (lib "eagle-import") (part "22-?-0327-2031"))
    )
    (comp (ref "U3")
      (value "SN65176BD")
      (footprint "eagle-import:DIL8")
      (libsource (lib "eagle-import") (part "MAX485_DIP"))
    )
    (comp (ref "X1")
      (value "DB9 femmina")
      (footprint "eagle-import:F09HP")
      (libsource (lib "eagle-import") (part "F09HP"))
    )
    (comp (ref "XB1")
      (value "MAXSTREAM_XBEE-PRO")
      (footprint "eagle-import:MAXSTREAM_XBEE-PRO")
      (libsource (lib "eagle-import") (part "MAXSTREAM_XBEE-PRO"))
    )
    (comp (ref "IC1B")
      (value "74HC4067DB")
      (footprint "eagle-import:DIL24-6")
      (libsource (lib "eagle-import") (part "4067N"))
    )
    (comp (ref "IC2B")
      (value "74HC4067DB")
      (footprint "eagle-import:DIL24-6")
      (libsource (lib "eagle-import") (part "4067N"))
    )
    (comp (ref "CN3")
      (value "SATA-7")
      (footprint "eagle-import:SATA-5607-5102-SH")
      (libsource (lib "eagle-import") (part "SATA-7"))
    )
    (comp (ref "CN4")
      (value "SATA-7")
      (footprint "eagle-import:SATA-5607-5102-SH")
      (libsource (lib "eagle-import") (part "SATA-7"))
    )
    (comp (ref "ENC_1")
      (value "J2541406-R")
      (footprint "eagle-import:6410-06")
      (libsource (lib "eagle-import") (part "22-?-0627-2061"))
    )
    (comp (ref "ENC_2")
      (value "J2541406-R")
      (footprint "eagle-import:6410-06")
      (libsource (lib "eagle-import") (part "22-?-0627-2061"))
    )
    (comp (ref "JP4")
      (value "STREP3x2VERT")
      (footprint "eagle-import:JP3Q")
      (libsource (lib "eagle-import") (part "JP3Q"))
    )
    (comp (ref "JP5")
      (value "STREP3x2VERT")
      (footprint "eagle-import:JP3Q")
      (libsource (lib "eagle-import") (part "JP3Q"))
    )
    (comp (ref "JP6")
      (value "STREP3x2VERT")
      (footprint "eagle-import:JP3Q")
      (libsource (lib "eagle-import") (part "JP3Q"))
    )
    (comp (ref "JP7")
      (value "STREP3x2VERT")
      (footprint "eagle-import:JP3Q")
      (libsource (lib "eagle-import") (part "JP3Q"))
    )
    (comp (ref "MOT_1")
      (value "J2541406-R")
      (footprint "eagle-import:6410-06")
      (libsource (lib "eagle-import") (part "22-?-0627-2061"))
    )
    (comp (ref "MOT_2")
      (value "J2541406-R")
      (footprint "eagle-import:6410-06")
      (libsource (lib "eagle-import") (part "22-?-0627-2061"))
    )
    (comp (ref "POW")
      (value "J2541406-R")
      (footprint "eagle-import:6410-06")
      (libsource (lib "eagle-import") (part "22-?-0627-2061"))
    )
    (comp (ref "R57")
      (value "10K")
      (footprint "eagle-import:0207_7")
      (libsource (lib "eagle-import") (part "R-EU_0207/7"))
    )
    (comp (ref "R58")
      (value "10K")
      (footprint "eagle-import:0207_7")
      (libsource (lib "eagle-import") (part "R-EU_0207/7"))
    )
    (comp (ref "R59")
      (value "10K")
      (footprint "eagle-import:0207_7")
      (libsource (lib "eagle-import") (part "R-EU_0207/7"))
    )
    (comp (ref "R60")
      (value "22K")
      (footprint "eagle-import:0207_7")
      (libsource (lib "eagle-import") (part "R-EU_0207/7"))
    )
    (comp (ref "R61")
      (value "22K")
      (footprint "eagle-import:0207_7")
      (libsource (lib "eagle-import") (part "R-EU_0207/7"))
    )
    (comp (ref "R62")
      (value "22K")
      (footprint "eagle-import:0207_7")
      (libsource (lib "eagle-import") (part "R-EU_0207/7"))
    )
    (comp (ref "R63")
      (value "4K7")
      (footprint "eagle-import:0207_7")
      (libsource (lib "eagle-import") (part "R-EU_0207/7"))
    )
    (comp (ref "R64")
      (value "4K7")
      (footprint "eagle-import:0207_7")
      (libsource (lib "eagle-import") (part "R-EU_0207/7"))
    )
    (comp (ref "R65")
      (value "4K7")
      (footprint "eagle-import:0207_7")
      (libsource (lib "eagle-import") (part "R-EU_0207/7"))
    )
    (comp (ref "R66")
      (value "10K")
      (footprint "eagle-import:0207_7")
      (libsource (lib "eagle-import") (part "R-EU_0207/7"))
    )
    (comp (ref "R67")
      (value "10K")
      (footprint "eagle-import:0207_7")
      (libsource (lib "eagle-import") (part "R-EU_0207/7"))
    )
    (comp (ref "R68")
      (value "10K")
      (footprint "eagle-import:0207_7")
      (libsource (lib "eagle-import") (part "R-EU_0207/7"))
    )
    (comp (ref "R69")
      (value "22K")
      (footprint "eagle-import:0207_7")
      (libsource (lib "eagle-import") (part "R-EU_0207/7"))
    )
    (comp (ref "R70")
      (value "22K")
      (footprint "eagle-import:0207_7")
      (libsource (lib "eagle-import") (part "R-EU_0207/7"))
    )
    (comp (ref "R71")
      (value "22K")
      (footprint "eagle-import:0207_7")
      (libsource (lib "eagle-import") (part "R-EU_0207/7"))
    )
    (comp (ref "R72")
      (value "4K7")
      (footprint "eagle-import:0207_7")
      (libsource (lib "eagle-import") (part "R-EU_0207/7"))
    )
    (comp (ref "R73")
      (value "4K7")
      (footprint "eagle-import:0207_7")
      (libsource (lib "eagle-import") (part "R-EU_0207/7"))
    )
    (comp (ref "R74")
      (value "4K7")
      (footprint "eagle-import:0207_7")
      (libsource (lib "eagle-import") (part "R-EU_0207/7"))
    )
    (comp (ref "C1")
      (value "CPOL-EUE5-13")
      (footprint "eagle-import:E5-13")
      (libsource (lib "eagle-import") (part "CPOL-EUE5-13"))
    )
    (comp (ref "C2")
      (value "100nF p5.08")
      (footprint "eagle-import:C050-024X044")
      (libsource (lib "eagle-import") (part "C-EU050-024X044"))
    )
    (comp (ref "C3")
      (value "100nF p5.08")
      (footprint "eagle-import:C050-024X044")
      (libsource (lib "eagle-import") (part "C-EU050-024X044"))
    )
    (comp (ref "C4")
      (value "470uF 16V P3,5 D8")
      (footprint "eagle-import:E3,5-8")
      (libsource (lib "eagle-import") (part "CPOL-EUE3.5-8"))
    )
    (comp (ref "C6")
      (value "470uF 16V P3,5 D8")
      (footprint "eagle-import:E3,5-8")
      (libsource (lib "eagle-import") (part "CPOL-EUE3.5-8"))
    )
    (comp (ref "C7")
      (value "100nF p5.08")
      (footprint "eagle-import:C050-024X044")
      (libsource (lib "eagle-import") (part "C-EU050-024X044"))
    )
    (comp (ref "C8")
      (value "100nF p5.08")
      (footprint "eagle-import:C050-024X044")
      (libsource (lib "eagle-import") (part "C-EU050-024X044"))
    )
    (comp (ref "C9")
      (value "100nF p5.08")
      (footprint "eagle-import:C050-024X044")
      (libsource (lib "eagle-import") (part "C-EU050-024X044"))
    )
    (comp (ref "CN1")
      (value "10.8060.0008")
      (footprint "eagle-import:300-021-13_2P_5VE")
      (libsource (lib "eagle-import") (part "10.8060.0008"))
    )
    (comp (ref "D1")
      (value "1N4007")
      (footprint "eagle-import:D041-10")
      (libsource (lib "eagle-import") (part "1N4007"))
    )
    (comp (ref "DIS1")
      (value "STM32F4-DISCOVERY")
      (footprint "eagle-import:STM32F4-DISCOVERY")
      (libsource (lib "eagle-import") (part "STM32F4-DISCOVERY"))
    )
    (comp (ref "H1")
      (value "MOUNT-PAD-ROUND3.3")
      (footprint "eagle-import:3,3-PAD")
      (libsource (lib "eagle-import") (part "MOUNT-PAD-ROUND3.3"))
    )
    (comp (ref "H2")
      (value "MOUNT-PAD-ROUND3.3")
      (footprint "eagle-import:3,3-PAD")
      (libsource (lib "eagle-import") (part "MOUNT-PAD-ROUND3.3"))
    )
    (comp (ref "H3")
      (value "MOUNT-PAD-ROUND3.3")
      (footprint "eagle-import:3,3-PAD")
      (libsource (lib "eagle-import") (part "MOUNT-PAD-ROUND3.3"))
    )
    (comp (ref "H4")
      (value "MOUNT-PAD-ROUND3.3")
      (footprint "eagle-import:3,3-PAD")
      (libsource (lib "eagle-import") (part "MOUNT-PAD-ROUND3.3"))
    )
    (comp (ref "JP1")
      (value "JP1E")
      (footprint "eagle-import:JP1")
      (libsource (lib "eagle-import") (part "JP1E"))
    )
    (comp (ref "JP2")
      (value "M07LONGPADS")
      (footprint "eagle-import:1X07_LONGPADS")
      (libsource (lib "eagle-import") (part "M07LONGPADS"))
    )
    (comp (ref "KK1")
      (value "SK13/35")
      (footprint "eagle-import:SK13_35")
      (libsource (lib "eagle-import") (part "SK13/35"))
    )
    (comp (ref "KK4")
      (value "SK13/35")
      (footprint "eagle-import:SK13_35")
      (libsource (lib "eagle-import") (part "SK13/35"))
    )
    (comp (ref "LOGO1")
      (value "OSHW-LOGOM")
      (footprint "eagle-import:OSHW-LOGO-M")
      (libsource (lib "eagle-import") (part "OSHW-LOGOM"))
    )
    (comp (ref "P1")
      (value "PULS6X6SMD")
      (footprint "eagle-import:PULS6X6SMD")
      (libsource (lib "eagle-import") (part "PULS6X6SMD"))
    )
    (comp (ref "P2")
      (value "PULS6X6SMD")
      (footprint "eagle-import:PULS6X6SMD")
      (libsource (lib "eagle-import") (part "PULS6X6SMD"))
    )
    (comp (ref "R1")
      (value "0R")
      (footprint "eagle-import:0207_7")
      (libsource (lib "eagle-import") (part "R-EU_0207/7"))
    )
    (comp (ref "R2")
      (value "0R")
      (footprint "eagle-import:0207_7")
      (libsource (lib "eagle-import") (part "R-EU_0207/7"))
    )
    (comp (ref "R87")
      (value "10K")
      (footprint "eagle-import:0207_7")
      (libsource (lib "eagle-import") (part "R-EU_0207/7"))
    )
    (comp (ref "R88")
      (value "10K")
      (footprint "eagle-import:0207_7")
      (libsource (lib "eagle-import") (part "R-EU_0207/7"))
    )
    (comp (ref "U1")
      (value "L78XXAB/AC")
      (footprint "eagle-import:78XXL")
      (libsource (lib "eagle-import") (part "L78XXAB/AC"))
    )
    (comp (ref "U2")
      (value "LD1117V33")
      (footprint "eagle-import:317TL")
      (libsource (lib "eagle-import") (part "LM317TL"))
    )
  )
  (nets
    (net (code "1") (name "+3V3") (class "Default")
      (node (ref "C2") (pin "1") (pinfunction "1_1") (pintype "passive"))
      (node (ref "C36") (pin "2") (pinfunction "2_2") (pintype "passive"))
      (node (ref "C37") (pin "-") (pinfunction "-_-") (pintype "passive"))
      (node (ref "C40") (pin "+") (pinfunction "+_+") (pintype "passive"))
      (node (ref "C41") (pin "1") (pinfunction "1_1") (pintype "passive"))
      (node (ref "C6") (pin "+") (pinfunction "+_+") (pintype "passive"))
      (node (ref "C7") (pin "1") (pinfunction "1_1") (pintype "passive"))
      (node (ref "C8") (pin "1") (pinfunction "1_1") (pintype "passive"))
      (node (ref "DIS1") (pin "3") (pinfunction "VDD_3") (pintype "bidirectional"))
      (node (ref "DIS1") (pin "4") (pinfunction "VDD1_4") (pintype "bidirectional"))
      (node (ref "DIS1") (pin "55") (pinfunction "VDD2_55") (pintype "bidirectional"))
      (node (ref "DIS1") (pin "56") (pinfunction "VDD3_56") (pintype "bidirectional"))
      (node (ref "DIS1") (pin "72") (pinfunction "VDD4_72") (pintype "bidirectional"))
      (node (ref "IC4") (pin "16") (pinfunction "VCC_16") (pintype "power_in"))
      (node (ref "POW") (pin "2") (pinfunction "S_2") (pintype "passive"))
      (node (ref "R2") (pin "1") (pinfunction "1_1") (pintype "passive"))
      (node (ref "R76") (pin "1") (pinfunction "1_1") (pintype "passive"))
      (node (ref "R78") (pin "1") (pinfunction "1_1") (pintype "passive"))
      (node (ref "R87") (pin "1") (pinfunction "1_1") (pintype "passive"))
      (node (ref "R88") (pin "1") (pinfunction "1_1") (pintype "passive"))
      (node (ref "U2") (pin "2") (pinfunction "OUT_2") (pintype "passive"))
      (node (ref "XB1") (pin "1") (pinfunction "VCC_1") (pintype "power_in"))
    )
    (net (code "2") (name "+5V") (class "Default")
      (node (ref "C3") (pin "1") (pinfunction "1_1") (pintype "passive"))
      (node (ref "C39") (pin "1") (pinfunction "1_1") (pintype "passive"))
      (node (ref "C4") (pin "+") (pinfunction "+_+") (pintype "passive"))
      (node (ref "C9") (pin "1") (pinfunction "1_1") (pintype "passive"))
      (node (ref "DIS1") (pin "53") (pinfunction "5V_53") (pintype "bidirectional"))
      (node (ref "DIS1") (pin "54") (pinfunction "5V2_54") (pintype "bidirectional"))
      (node (ref "ENC_1") (pin "6") (pinfunction "S_6") (pintype "passive"))
      (node (ref "ENC_2") (pin "6") (pinfunction "S_6") (pintype "passive"))
      (node (ref "JP1") (pin "2") (pinfunction "2_2") (pintype "passive"))
      (node (ref "JP3") (pin "1") (pinfunction "1_1") (pintype "passive"))
      (node (ref "JP4") (pin "2") (pinfunction "2_2") (pintype "passive"))
      (node (ref "JP4") (pin "4") (pinfunction "4_4") (pintype "passive"))
      (node (ref "JP4") (pin "6") (pinfunction "6_6") (pintype "passive"))
      (node (ref "JP6") (pin "2") (pinfunction "2_2") (pintype "passive"))
      (node (ref "JP6") (pin "4") (pinfunction "4_4") (pintype "passive"))
      (node (ref "JP6") (pin "6") (pinfunction "6_6") (pintype "passive"))
      (node (ref "MOT_1") (pin "1") (pinfunction "S_1") (pintype "passive"))
      (node (ref "MOT_2") (pin "1") (pinfunction "S_1") (pintype "passive"))
      (node (ref "POW") (pin "4") (pinfunction "S_4") (pintype "passive"))
      (node (ref "R1") (pin "1") (pinfunction "1_1") (pintype "passive"))
      (node (ref "R75") (pin "1") (pinfunction "1_1") (pintype "passive"))
      (node (ref "R77") (pin "1") (pinfunction "1_1") (pintype "passive"))
      (node (ref "R85") (pin "1") (pinfunction "1_1") (pintype "passive"))
      (node (ref "U1") (pin "OUT") (pinfunction "OUT_OUT") (pintype "passive"))
      (node (ref "U2") (pin "3") (pinfunction "IN_3") (pintype "input"))
      (node (ref "U3") (pin "8") (pinfunction "VCC_8") (pintype "bidirectional"))
    )
    (net (code "3") (name "+5V{slash}1") (class "Default")
      (node (ref "C12") (pin "1") (pinfunction "1_1") (pintype "passive"))
      (node (ref "C13") (pin "1") (pinfunction "1_1") (pintype "passive"))
      (node (ref "C14") (pin "1") (pinfunction "1_1") (pintype "passive"))
      (node (ref "C15") (pin "1") (pinfunction "1_1") (pintype "passive"))
      (node (ref "C16") (pin "1") (pinfunction "1_1") (pintype "passive"))
      (node (ref "C17") (pin "1") (pinfunction "1_1") (pintype "passive"))
      (node (ref "C18") (pin "1") (pinfunction "1_1") (pintype "passive"))
      (node (ref "C19") (pin "1") (pinfunction "1_1") (pintype "passive"))
      (node (ref "C20") (pin "1") (pinfunction "1_1") (pintype "passive"))
      (node (ref "C21") (pin "1") (pinfunction "1_1") (pintype "passive"))
      (node (ref "C22") (pin "1") (pinfunction "1_1") (pintype "passive"))
      (node (ref "C23") (pin "1") (pinfunction "1_1") (pintype "passive"))
      (node (ref "C24") (pin "1") (pinfunction "1_1") (pintype "passive"))
      (node (ref "C25") (pin "1") (pinfunction "1_1") (pintype "passive"))
      (node (ref "C26") (pin "1") (pinfunction "1_1") (pintype "passive"))
      (node (ref "C27") (pin "1") (pinfunction "1_1") (pintype "passive"))
      (node (ref "C28") (pin "1") (pinfunction "1_1") (pintype "passive"))
      (node (ref "C29") (pin "1") (pinfunction "1_1") (pintype "passive"))
      (node (ref "C31") (pin "+") (pinfunction "+_+") (pintype "passive"))
      (node (ref "IC1") (pin "24") (pinfunction "VDD_24") (pintype "power_in"))
      (node (ref "IC1B") (pin "24") (pinfunction "VDD_24") (pintype "power_in"))
      (node (ref "IC2") (pin "24") (pinfunction "VDD_24") (pintype "power_in"))
      (node (ref "IC2B") (pin "24") (pinfunction "VDD_24") (pintype "power_in"))
      (node (ref "IC3") (pin "10") (pinfunction "CD+_10") (pintype "passive"))
      (node (ref "L1") (pin "2") (pinfunction "2_2") (pintype "passive"))
      (node (ref "POW") (pin "6") (pinfunction "S_6") (pintype "passive"))
      (node (ref "Q1") (pin "E") (pinfunction "E_E") (pintype "passive"))
      (node (ref "Q2") (pin "E") (pinfunction "E_E") (pintype "passive"))
      (node (ref "Q3") (pin "E") (pinfunction "E_E") (pintype "passive"))
      (node (ref "Q4") (pin "E") (pinfunction "E_E") (pintype "passive"))
      (node (ref "Q5") (pin "E") (pinfunction "E_E") (pintype "passive"))
      (node (ref "Q6") (pin "E") (pinfunction "E_E") (pintype "passive"))
      (node (ref "SN1") (pin "1") (pinfunction "S_1") (pintype "passive"))
      (node (ref "SN10") (pin "1") (pinfunction "S_1") (pintype "passive"))
      (node (ref "SN11") (pin "1") (pinfunction "S_1") (pintype "passive"))
      (node (ref "SN12") (pin "1") (pinfunction "S_1") (pintype "passive"))
      (node (ref "SN13") (pin "1") (pinfunction "S_1") (pintype "passive"))
      (node (ref "SN14") (pin "1") (pinfunction "S_1") (pintype "passive"))
      (node (ref "SN15") (pin "1") (pinfunction "S_1") (pintype "passive"))
      (node (ref "SN16") (pin "1") (pinfunction "S_1") (pintype "passive"))
      (node (ref "SN2") (pin "1") (pinfunction "S_1") (pintype "passive"))
      (node (ref "SN3") (pin "1") (pinfunction "S_1") (pintype "passive"))
      (node (ref "SN4") (pin "1") (pinfunction "S_1") (pintype "passive"))
      (node (ref "SN5") (pin "1") (pinfunction "S_1") (pintype "passive"))
      (node (ref "SN6") (pin "1") (pinfunction "S_1") (pintype "passive"))
      (node (ref "SN7") (pin "1") (pinfunction "S_1") (pintype "passive"))
      (node (ref "SN8") (pin "1") (pinfunction "S_1") (pintype "passive"))
      (node (ref "SN9") (pin "1") (pinfunction "S_1") (pintype "passive"))
    )
    (net (code "4") (name "A") (class "Default")
      (node (ref "JP11") (pin "6") (pinfunction "6_6") (pintype "passive"))
      (node (ref "R80") (pin "2") (pinfunction "2_2") (pintype "passive"))
      (node (ref "R83") (pin "1") (pinfunction "1_1") (pintype "passive"))
      (node (ref "RS1") (pin "3") (pinfunction "S_3") (pintype "passive"))
      (node (ref "U3") (pin "6") (pinfunction "A_6") (pintype "passive"))
    )
    (net (code "5") (name "A1") (class "Default")
      (node (ref "ENC_1") (pin "4") (pinfunction "S_4") (pintype "passive"))
      (node (ref "R57") (pin "1") (pinfunction "1_1") (pintype "passive"))
      (node (ref "R60") (pin "2") (pinfunction "2_2") (pintype "passive"))
    )
    (net (code "6") (name "A2") (class "Default")
      (node (ref "ENC_2") (pin "4") (pinfunction "S_4") (pintype "passive"))
      (node (ref "R66") (pin "1") (pinfunction "1_1") (pintype "passive"))
      (node (ref "R69") (pin "2") (pinfunction "2_2") (pintype "passive"))
    )
    (net (code "7") (name "B") (class "Default")
      (node (ref "JP11") (pin "2") (pinfunction "2_2") (pintype "passive"))
      (node (ref "JP11") (pin "4") (pinfunction "4_4") (pintype "passive"))
      (node (ref "R86") (pin "1") (pinfunction "1_1") (pintype "passive"))
      (node (ref "RS1") (pin "1") (pinfunction "S_1") (pintype "passive"))
      (node (ref "U3") (pin "7") (pinfunction "B_7") (pintype "passive"))
    )
    (net (code "8") (name "B1") (class "Default")
      (node (ref "ENC_1") (pin "3") (pinfunction "S_3") (pintype "passive"))
      (node (ref "R58") (pin "1") (pinfunction "1_1") (pintype "passive"))
      (node (ref "R61") (pin "2") (pinfunction "2_2") (pintype "passive"))
    )
    (net (code "9") (name "B2") (class "Default")
      (node (ref "ENC_2") (pin "3") (pinfunction "S_3") (pintype "passive"))
      (node (ref "R67") (pin "1") (pinfunction "1_1") (pintype "passive"))
      (node (ref "R70") (pin "2") (pinfunction "2_2") (pintype "passive"))
    )
    (net (code "10") (name "BMP085_CLR") (class "Default")
      (node (ref "DIS1") (pin "32") (pinfunction "PE14_32") (pintype "bidirectional"))
      (node (ref "JP2") (pin "3") (pinfunction "3_3") (pintype "passive"))
    )
    (net (code "11") (name "BMP085_EOC") (class "Default")
      (node (ref "DIS1") (pin "33") (pinfunction "PE15_33") (pintype "bidirectional"))
      (node (ref "JP2") (pin "2") (pinfunction "2_2") (pintype "passive"))
    )
    (net (code "12") (name "BMP085_SCL") (class "Default")
      (node (ref "DIS1") (pin "34") (pinfunction "PB10_34") (pintype "bidirectional"))
      (node (ref "JP2") (pin "4") (pinfunction "4_4") (pintype "passive"))
    )
    (net (code "13") (name "BMP085_SDA") (class "Default")
      (node (ref "DIS1") (pin "35") (pinfunction "PB11_35") (pintype "bidirectional"))
      (node (ref "JP2") (pin "5") (pinfunction "5_5") (pintype "passive"))
    )
    (net (code "14") (name "COM1-RX") (class "Default")
      (node (ref "JP12") (pin "2") (pinfunction "2_2") (pintype "passive"))
      (node (ref "XB1") (pin "2") (pinfunction "DOUT_2") (pintype "output"))
    )
    (net (code "15") (name "COM1-TX") (class "Default")
      (node (ref "JP12") (pin "4") (pinfunction "4_4") (pintype "passive"))
      (node (ref "XB1") (pin "3") (pinfunction "DIN/~{CONFIG}_3") (pintype "input"))
    )
    (net (code "16") (name "ECHO_MUX") (class "Default")
      (node (ref "DIS1") (pin "38") (pinfunction "PB14_38") (pintype "bidirectional"))
      (node (ref "IC2") (pin "1") (pinfunction "X_1") (pintype "output"))
      (node (ref "IC2B") (pin "1") (pinfunction "X_1") (pintype "output"))
    )
    (net (code "17") (name "ECHO_U1") (class "Default")
      (node (ref "IC2") (pin "9") (pinfunction "X0_9") (pintype "input"))
      (node (ref "IC2B") (pin "9") (pinfunction "X0_9") (pintype "input"))
      (node (ref "SN1") (pin "3") (pinfunction "S_3") (pintype "passive"))
    )
    (net (code "18") (name "ECHO_U2") (class "Default")
      (node (ref "IC2") (pin "8") (pinfunction "X1_8") (pintype "input"))
      (node (ref "IC2B") (pin "8") (pinfunction "X1_8") (pintype "input"))
      (node (ref "SN2") (pin "3") (pinfunction "S_3") (pintype "passive"))
    )
    (net (code "19") (name "ECHO_U3") (class "Default")
      (node (ref "IC2") (pin "7") (pinfunction "X2_7") (pintype "input"))
      (node (ref "IC2B") (pin "7") (pinfunction "X2_7") (pintype "input"))
      (node (ref "SN3") (pin "3") (pinfunction "S_3") (pintype "passive"))
    )
    (net (code "20") (name "ECHO_U4") (class "Default")
      (node (ref "IC2") (pin "6") (pinfunction "X3_6") (pintype "input"))
      (node (ref "IC2B") (pin "6") (pinfunction "X3_6") (pintype "input"))
      (node (ref "SN4") (pin "3") (pinfunction "S_3") (pintype "passive"))
    )
    (net (code "21") (name "ECHO_U5") (class "Default")
      (node (ref "IC2") (pin "5") (pinfunction "X4_5") (pintype "input"))
      (node (ref "IC2B") (pin "5") (pinfunction "X4_5") (pintype "input"))
      (node (ref "SN5") (pin "3") (pinfunction "S_3") (pintype "passive"))
    )
    (net (code "22") (name "ECHO_U6") (class "Default")
      (node (ref "IC2") (pin "4") (pinfunction "X5_4") (pintype "input"))
      (node (ref "IC2B") (pin "4") (pinfunction "X5_4") (pintype "input"))
      (node (ref "SN6") (pin "3") (pinfunction "S_3") (pintype "passive"))
    )
    (net (code "23") (name "ECHO_U7") (class "Default")
      (node (ref "IC2") (pin "3") (pinfunction "X6_3") (pintype "input"))
      (node (ref "IC2B") (pin "3") (pinfunction "X6_3") (pintype "input"))
      (node (ref "SN7") (pin "3") (pinfunction "S_3") (pintype "passive"))
    )
    (net (code "24") (name "ECHO_U8") (class "Default")
      (node (ref "IC2") (pin "2") (pinfunction "X7_2") (pintype "input"))
      (node (ref "IC2B") (pin "2") (pinfunction "X7_2") (pintype "input"))
      (node (ref "SN8") (pin "3") (pinfunction "S_3") (pintype "passive"))
    )
    (net (code "25") (name "ECHO_U9") (class "Default")
      (node (ref "IC2") (pin "23") (pinfunction "X8_23") (pintype "input"))
      (node (ref "IC2B") (pin "23") (pinfunction "X8_23") (pintype "input"))
      (node (ref "SN9") (pin "3") (pinfunction "S_3") (pintype "passive"))
    )
    (net (code "26") (name "ECHO_U10") (class "Default")
      (node (ref "IC2") (pin "22") (pinfunction "X9_22") (pintype "input"))
      (node (ref "IC2B") (pin "22") (pinfunction "X9_22") (pintype "input"))
      (node (ref "SN10") (pin "3") (pinfunction "S_3") (pintype "passive"))
    )
    (net (code "27") (name "ECHO_U11") (class "Default")
      (node (ref "IC2") (pin "21") (pinfunction "X10_21") (pintype "input"))
      (node (ref "IC2B") (pin "21") (pinfunction "X10_21") (pintype "input"))
      (node (ref "SN11") (pin "3") (pinfunction "S_3") (pintype "passive"))
    )
    (net (code "28") (name "ECHO_U12") (class "Default")
      (node (ref "IC2") (pin "20") (pinfunction "X11_20") (pintype "input"))
      (node (ref "IC2B") (pin "20") (pinfunction "X11_20") (pintype "input"))
      (node (ref "SN12") (pin "3") (pinfunction "S_3") (pintype "passive"))
    )
    (net (code "29") (name "ECHO_U13") (class "Default")
      (node (ref "IC2") (pin "19") (pinfunction "X12_19") (pintype "input"))
      (node (ref "IC2B") (pin "19") (pinfunction "X12_19") (pintype "input"))
      (node (ref "SN13") (pin "3") (pinfunction "S_3") (pintype "passive"))
    )
    (net (code "30") (name "ECHO_U14") (class "Default")
      (node (ref "IC2") (pin "18") (pinfunction "X13_18") (pintype "input"))
      (node (ref "IC2B") (pin "18") (pinfunction "X13_18") (pintype "input"))
      (node (ref "SN14") (pin "3") (pinfunction "S_3") (pintype "passive"))
    )
    (net (code "31") (name "ECHO_U15") (class "Default")
      (node (ref "IC2") (pin "17") (pinfunction "X14_17") (pintype "input"))
      (node (ref "IC2B") (pin "17") (pinfunction "X14_17") (pintype "input"))
      (node (ref "SN15") (pin "3") (pinfunction "S_3") (pintype "passive"))
    )
    (net (code "32") (name "ECHO_U16") (class "Default")
      (node (ref "IC2") (pin "16") (pinfunction "X15_16") (pintype "input"))
      (node (ref "IC2B") (pin "16") (pinfunction "X15_16") (pintype "input"))
      (node (ref "SN16") (pin "3") (pinfunction "S_3") (pintype "passive"))
    )
    (net (code "33") (name "ENC1_A") (class "Default")
      (node (ref "DIS1") (pin "15") (pinfunction "PA5_15") (pintype "bidirectional"))
      (node (ref "R60") (pin "1") (pinfunction "1_1") (pintype "passive"))
      (node (ref "R63") (pin "2") (pinfunction "2_2") (pintype "passive"))
    )
    (net (code "34") (name "ENC1_B") (class "Default")
      (node (ref "DIS1") (pin "11") (pinfunction "PA1_11") (pintype "bidirectional"))
      (node (ref "R61") (pin "1") (pinfunction "1_1") (pintype "passive"))
      (node (ref "R64") (pin "2") (pinfunction "2_2") (pintype "passive"))
    )
    (net (code "35") (name "ENC1_IDX") (class "Default")
      (node (ref "DIS1") (pin "20") (pinfunction "PC4_20") (pintype "bidirectional"))
      (node (ref "R62") (pin "1") (pinfunction "1_1") (pintype "passive"))
      (node (ref "R65") (pin "2") (pinfunction "2_2") (pintype "passive"))
    )
    (net (code "36") (name "ENC2_A") (class "Default")
      (node (ref "DIS1") (pin "18") (pinfunction "PA6_18") (pintype "bidirectional"))
      (node (ref "R69") (pin "1") (pinfunction "1_1") (pintype "passive"))
      (node (ref "R72") (pin "2") (pinfunction "2_2") (pintype "passive"))
    )
    (net (code "37") (name "ENC2_B") (class "Default")
      (node (ref "DIS1") (pin "17") (pinfunction "PA7_17") (pintype "bidirectional"))
      (node (ref "R70") (pin "1") (pinfunction "1_1") (pintype "passive"))
      (node (ref "R73") (pin "2") (pinfunction "2_2") (pintype "passive"))
    )
    (net (code "38") (name "ENC2_IDX") (class "Default")
      (node (ref "DIS1") (pin "16") (pinfunction "PA4_16") (pintype "bidirectional"))
      (node (ref "R71") (pin "1") (pinfunction "1_1") (pintype "passive"))
      (node (ref "R74") (pin "2") (pinfunction "2_2") (pintype "passive"))
    )
    (net (code "39") (name "F4_UART1_DIR") (class "Default")
      (node (ref "DIS1") (pin "76") (pinfunction "PB5_76") (pintype "bidirectional"))
      (node (ref "J1") (pin "2") (pinfunction "S_2") (pintype "passive"))
      (node (ref "JP9") (pin "4") (pinfunction "4_4") (pintype "passive"))
    )
    (net (code "40") (name "F4_UART1_RX") (class "Default")
      (node (ref "DIS1") (pin "74") (pinfunction "PB7_74") (pintype "bidirectional"))
      (node (ref "J1") (pin "3") (pinfunction "S_3") (pintype "passive"))
      (node (ref "JP9") (pin "6") (pinfunction "6_6") (pintype "passive"))
    )
    (net (code "41") (name "F4_UART1_TX") (class "Default")
      (node (ref "DIS1") (pin "73") (pinfunction "PB6_73") (pintype "bidirectional"))
      (node (ref "J1") (pin "4") (pinfunction "S_4") (pintype "passive"))
      (node (ref "JP9") (pin "2") (pinfunction "2_2") (pintype "passive"))
    )
    (net (code "42") (name "F4_UART2_DIR") (class "Default")
      (node (ref "DIS1") (pin "19") (pinfunction "PC5_19") (pintype "bidirectional"))
      (node (ref "J2") (pin "2") (pinfunction "S_2") (pintype "passive"))
    )
    (net (code "43") (name "F4_UART2_RX") (class "Default")
      (node (ref "DIS1") (pin "13") (pinfunction "PA3_13") (pintype "bidirectional"))
      (node (ref "J2") (pin "3") (pinfunction "S_3") (pintype "passive"))
      (node (ref "JP12") (pin "1") (pinfunction "1_1") (pintype "passive"))
      (node (ref "JP8") (pin "2") (pinfunction "2_2") (pintype "passive"))
    )
    (net (code "44") (name "F4_UART2_TX") (class "Default")
      (node (ref "DIS1") (pin "14") (pinfunction "PA2_14") (pintype "bidirectional"))
      (node (ref "J2") (pin "4") (pinfunction "S_4") (pintype "passive"))
      (node (ref "JP12") (pin "3") (pinfunction "3_3") (pintype "passive"))
      (node (ref "JP8") (pin "4") (pinfunction "4_4") (pintype "passive"))
    )
    (net (code "45") (name "GND") (class "Default")
      (node (ref "C1") (pin "-") (pinfunction "-_-") (pintype "passive"))
      (node (ref "C12") (pin "2") (pinfunction "2_2") (pintype "passive"))
      (node (ref "C13") (pin "2") (pinfunction "2_2") (pintype "passive"))
      (node (ref "C14") (pin "2") (pinfunction "2_2") (pintype "passive"))
      (node (ref "C15") (pin "2") (pinfunction "2_2") (pintype "passive"))
      (node (ref "C16") (pin "2") (pinfunction "2_2") (pintype "passive"))
      (node (ref "C17") (pin "2") (pinfunction "2_2") (pintype "passive"))
      (node (ref "C18") (pin "2") (pinfunction "2_2") (pintype "passive"))
      (node (ref "C19") (pin "2") (pinfunction "2_2") (pintype "passive"))
      (node (ref "C2") (pin "2") (pinfunction "2_2") (pintype "passive"))
      (node (ref "C20") (pin "2") (pinfunction "2_2") (pintype "passive"))
      (node (ref "C21") (pin "2") (pinfunction "2_2") (pintype "passive"))
      (node (ref "C22") (pin "2") (pinfunction "2_2") (pintype "passive"))
      (node (ref "C23") (pin "2") (pinfunction "2_2") (pintype "passive"))
      (node (ref "C24") (pin "2") (pinfunction "2_2") (pintype "passive"))
      (node (ref "C25") (pin "2") (pinfunction "2_2") (pintype "passive"))
      (node (ref "C26") (pin "2") (pinfunction "2_2") (pintype "passive"))
      (node (ref "C27") (pin "2") (pinfunction "2_2") (pintype "passive"))
      (node (ref "C28") (pin "2") (pinfunction "2_2") (pintype "passive"))
      (node (ref "C29") (pin "2") (pinfunction "2_2") (pintype "passive"))
      (node (ref "C3") (pin "2") (pinfunction "2_2") (pintype "passive"))
      (node (ref "C30") (pin "-") (pinfunction "-_-") (pintype "passive"))
      (node (ref "C31") (pin "-") (pinfunction "-_-") (pintype "passive"))
      (node (ref "C32") (pin "2") (pinfunction "2_2") (pintype "passive"))
      (node (ref "C33") (pin "2") (pinfunction "2_2") (pintype "passive"))
      (node (ref "C36") (pin "1") (pinfunction "1_1") (pintype "passive"))
      (node (ref "C38") (pin "+") (pinfunction "+_+") (pintype "passive"))
      (node (ref "C39") (pin "2") (pinfunction "2_2") (pintype "passive"))
      (node (ref "C4") (pin "-") (pinfunction "-_-") (pintype "passive"))
      (node (ref "C40") (pin "-") (pinfunction "-_-") (pintype "passive"))
      (node (ref "C41") (pin "2") (pinfunction "2_2") (pintype "passive"))
      (node (ref "C6") (pin "-") (pinfunction "-_-") (pintype "passive"))
      (node (ref "C7") (pin "2") (pinfunction "2_2") (pintype "passive"))
      (node (ref "C8") (pin "2") (pinfunction "2_2") (pintype "passive"))
      (node (ref "C9") (pin "2") (pinfunction "2_2") (pintype "passive"))
      (node (ref "CN1") (pin "1") (pinfunction "S_1") (pintype "passive"))
      (node (ref "CN2") (pin "1") (pinfunction "S_1") (pintype "passive"))
      (node (ref "CN3") (pin "1") (pinfunction "GND_1") (pintype "bidirectional"))
      (node (ref "CN3") (pin "4") (pinfunction "GND_4") (pintype "bidirectional"))
      (node (ref "CN3") (pin "7") (pinfunction "GND_7") (pintype "bidirectional"))
      (node (ref "CN3") (pin "H1") (pinfunction "H1_H1") (pintype "bidirectional"))
      (node (ref "CN3") (pin "H2") (pinfunction "H2_H2") (pintype "bidirectional"))
      (node (ref "CN4") (pin "1") (pinfunction "GND_1") (pintype "bidirectional"))
      (node (ref "CN4") (pin "4") (pinfunction "GND_4") (pintype "bidirectional"))
      (node (ref "CN4") (pin "7") (pinfunction "GND_7") (pintype "bidirectional"))
      (node (ref "CN4") (pin "H1") (pinfunction "H1_H1") (pintype "bidirectional"))
      (node (ref "CN4") (pin "H2") (pinfunction "H2_H2") (pintype "bidirectional"))
      (node (ref "DIS1") (pin "1") (pinfunction "GND_1") (pintype "bidirectional"))
      (node (ref "DIS1") (pin "100") (pinfunction "GND9_100") (pintype "bidirectional"))
      (node (ref "DIS1") (pin "2") (pinfunction "GND1_2") (pintype "bidirectional"))
      (node (ref "DIS1") (pin "23") (pinfunction "GND3_23") (pintype "bidirectional"))
      (node (ref "DIS1") (pin "49") (pinfunction "GND4_49") (pintype "bidirectional"))
      (node (ref "DIS1") (pin "5") (pinfunction "GND2_5") (pintype "bidirectional"))
      (node (ref "DIS1") (pin "50") (pinfunction "GND5_50") (pintype "bidirectional"))
      (node (ref "DIS1") (pin "51") (pinfunction "GND6_51") (pintype "bidirectional"))
      (node (ref "DIS1") (pin "52") (pinfunction "GND7_52") (pintype "bidirectional"))
      (node (ref "DIS1") (pin "99") (pinfunction "GND8_99") (pintype "bidirectional"))
      (node (ref "DIS1") (pin "G1") (pinfunction "G_G1") (pintype "bidirectional"))
      (node (ref "DIS1") (pin "G2") (pinfunction "G_G2") (pintype "bidirectional"))
      (node (ref "DIS1") (pin "G3") (pinfunction "G_G3") (pintype "bidirectional"))
      (node (ref "DIS1") (pin "G4") (pinfunction "G_G4") (pintype "bidirectional"))
      (node (ref "ENC_1") (pin "1") (pinfunction "S_1") (pintype "passive"))
      (node (ref "ENC_2") (pin "1") (pinfunction "S_1") (pintype "passive"))
      (node (ref "H1") (pin "B3,3") (pinfunction "MOUNT_B3,3") (pintype "passive"))
      (node (ref "H2") (pin "B3,3") (pinfunction "MOUNT_B3,3") (pintype "passive"))
      (node (ref "H3") (pin "B3,3") (pinfunction "MOUNT_B3,3") (pintype "passive"))
      (node (ref "H4") (pin "B3,3") (pinfunction "MOUNT_B3,3") (pintype "passive"))
      (node (ref "IC1") (pin "12") (pinfunction "VSS_12") (pintype "power_in"))
      (node (ref "IC1B") (pin "12") (pinfunction "VSS_12") (pintype "power_in"))
      (node (ref "IC2") (pin "12") (pinfunction "VSS_12") (pintype "power_in"))
      (node (ref "IC2B") (pin "12") (pinfunction "VSS_12") (pintype "power_in"))
      (node (ref "IC3") (pin "9") (pinfunction "GND_9") (pintype "power_in"))
      (node (ref "IC4") (pin "15") (pinfunction "GND_15") (pintype "power_in"))
      (node (ref "J1") (pin "5") (pinfunction "S_5") (pintype "passive"))
      (node (ref "J2") (pin "5") (pinfunction "S_5") (pintype "passive"))
      (node (ref "JP2") (pin "7") (pinfunction "7_7") (pintype "passive"))
      (node (ref "JP5") (pin "1") (pinfunction "1_1") (pintype "passive"))
      (node (ref "JP5") (pin "3") (pinfunction "3_3") (pintype "passive"))
      (node (ref "JP5") (pin "5") (pinfunction "5_5") (pintype "passive"))
      (node (ref "JP7") (pin "1") (pinfunction "1_1") (pintype "passive"))
      (node (ref "JP7") (pin "3") (pinfunction "3_3") (pintype "passive"))
      (node (ref "JP7") (pin "5") (pinfunction "5_5") (pintype "passive"))
      (node (ref "LED1") (pin "K") (pinfunction "C_K") (pintype "passive"))
      (node (ref "LED2") (pin "K") (pinfunction "C_K") (pintype "passive"))
      (node (ref "MOT_1") (pin "5") (pinfunction "S_5") (pintype "passive"))
      (node (ref "MOT_2") (pin "5") (pinfunction "S_5") (pintype "passive"))
      (node (ref "P1") (pin "3") (pinfunction "S1_3") (pintype "passive"))
      (node (ref "P1") (pin "4") (pinfunction "S_4") (pintype "passive"))
      (node (ref "P2") (pin "3") (pinfunction "S1_3") (pintype "passive"))
      (node (ref "P2") (pin "4") (pinfunction "S_4") (pintype "passive"))
      (node (ref "POW") (pin "1") (pinfunction "S_1") (pintype "passive"))
      (node (ref "POW") (pin "3") (pinfunction "S_3") (pintype "passive"))
      (node (ref "POW") (pin "5") (pinfunction "S_5") (pintype "passive"))
      (node (ref "R79") (pin "1") (pinfunction "1_1") (pintype "passive"))
      (node (ref "R84") (pin "2") (pinfunction "2_2") (pintype "passive"))
      (node (ref "RS1") (pin "2") (pinfunction "S_2") (pintype "passive"))
      (node (ref "SN1") (pin "4") (pinfunction "S_4") (pintype "passive"))
      (node (ref "SN10") (pin "4") (pinfunction "S_4") (pintype "passive"))
      (node (ref "SN11") (pin "4") (pinfunction "S_4") (pintype "passive"))
      (node (ref "SN12") (pin "4") (pinfunction "S_4") (pintype "passive"))
      (node (ref "SN13") (pin "4") (pinfunction "S_4") (pintype "passive"))
      (node (ref "SN14") (pin "4") (pinfunction "S_4") (pintype "passive"))
      (node (ref "SN15") (pin "4") (pinfunction "S_4") (pintype "passive"))
      (node (ref "SN16") (pin "4") (pinfunction "S_4") (pintype "passive"))
      (node (ref "SN2") (pin "4") (pinfunction "S_4") (pintype "passive"))
      (node (ref "SN3") (pin "4") (pinfunction "S_4") (pintype "passive"))
      (node (ref "SN4") (pin "4") (pinfunction "S_4") (pintype "passive"))
      (node (ref "SN5") (pin "4") (pinfunction "S_4") (pintype "passive"))
      (node (ref "SN6") (pin "4") (pinfunction "S_4") (pintype "passive"))
      (node (ref "SN7") (pin "4") (pinfunction "S_4") (pintype "passive"))
      (node (ref "SN8") (pin "4") (pinfunction "S_4") (pintype "passive"))
      (node (ref "SN9") (pin "4") (pinfunction "S_4") (pintype "passive"))
      (node (ref "U1") (pin "GND") (pinfunction "GND_GND") (pintype "input"))
      (node (ref "U2") (pin "1") (pinfunction "ADJ_1") (pintype "input"))
      (node (ref "U3") (pin "5") (pinfunction "GND_5") (pintype "bidirectional"))
      (node (ref "X1") (pin "5") (pinfunction "5_5") (pintype "passive"))
      (node (ref "X1") (pin "G1") (pinfunction "G1_G1") (pintype "passive"))
      (node (ref "X1") (pin "G2") (pinfunction "G2_G2") (pintype "passive"))
      (node (ref "XB1") (pin "10") (pinfunction "GND_10") (pintype "power_in"))
    )
    (net (code "46") (name "I1") (class "Default")
      (node (ref "ENC_1") (pin "2") (pinfunction "S_2") (pintype "passive"))
      (node (ref "R59") (pin "1") (pinfunction "1_1") (pintype "passive"))
      (node (ref "R62") (pin "2") (pinfunction "2_2") (pintype "passive"))
    )
    (net (code "47") (name "I2") (class "Default")
      (node (ref "ENC_2") (pin "2") (pinfunction "S_2") (pintype "passive"))
      (node (ref "R68") (pin "1") (pinfunction "1_1") (pintype "passive"))
      (node (ref "R71") (pin "2") (pinfunction "2_2") (pintype "passive"))
    )
    (net (code "48") (name "KLED_1") (class "Default")
      (node (ref "DIS1") (pin "80") (pinfunction "PD6_80") (pintype "bidirectional"))
      (node (ref "IC3") (pin "1") (pinfunction "I1_1") (pintype "input"))
    )
    (net (code "49") (name "KLED_2") (class "Default")
      (node (ref "DIS1") (pin "77") (pinfunction "PD7_77") (pintype "bidirectional"))
      (node (ref "IC3") (pin "2") (pinfunction "I2_2") (pintype "input"))
    )
    (net (code "50") (name "KLED_3") (class "Default")
      (node (ref "DIS1") (pin "40") (pinfunction "PD8_40") (pintype "bidirectional"))
      (node (ref "IC3") (pin "3") (pinfunction "I3_3") (pintype "input"))
    )
    (net (code "51") (name "KLED_4") (class "Default")
      (node (ref "DIS1") (pin "41") (pinfunction "PD9_41") (pintype "bidirectional"))
      (node (ref "IC3") (pin "4") (pinfunction "I4_4") (pintype "input"))
    )
    (net (code "52") (name "KLED_5") (class "Default")
      (node (ref "DIS1") (pin "42") (pinfunction "PD10_42") (pintype "bidirectional"))
      (node (ref "IC3") (pin "5") (pinfunction "I5_5") (pintype "input"))
    )
    (net (code "53") (name "KLED_6") (class "Default")
      (node (ref "DIS1") (pin "43") (pinfunction "PD11_43") (pintype "bidirectional"))
      (node (ref "IC3") (pin "6") (pinfunction "I6_6") (pintype "input"))
    )
    (net (code "54") (name "KLED_7") (class "Default")
      (node (ref "DIS1") (pin "44") (pinfunction "PD12_44") (pintype "bidirectional"))
      (node (ref "IC3") (pin "7") (pinfunction "I7_7") (pintype "input"))
    )
    (net (code "55") (name "KLED_8") (class "Default")
      (node (ref "DIS1") (pin "45") (pinfunction "PD13_45") (pintype "bidirectional"))
      (node (ref "IC3") (pin "8") (pinfunction "I8_8") (pintype "input"))
    )
    (net (code "56") (name "K_0") (class "Default")
      (node (ref "D2") (pin "2") (pinfunction "CATHODE_2") (pintype "bidirectional"))
      (node (ref "D3") (pin "2") (pinfunction "CATHODE_2") (pintype "bidirectional"))
      (node (ref "IC3") (pin "18") (pinfunction "O1_18") (pintype "open_collector"))
    )
    (net (code "57") (name "K_1") (class "Default")
      (node (ref "D4") (pin "2") (pinfunction "CATHODE_2") (pintype "bidirectional"))
      (node (ref "D5") (pin "2") (pinfunction "CATHODE_2") (pintype "bidirectional"))
      (node (ref "IC3") (pin "17") (pinfunction "O2_17") (pintype "open_collector"))
    )
    (net (code "58") (name "K_2") (class "Default")
      (node (ref "D6") (pin "2") (pinfunction "CATHODE_2") (pintype "bidirectional"))
      (node (ref "D7") (pin "2") (pinfunction "CATHODE_2") (pintype "bidirectional"))
      (node (ref "IC3") (pin "16") (pinfunction "O3_16") (pintype "open_collector"))
    )
    (net (code "59") (name "K_3") (class "Default")
      (node (ref "D8") (pin "2") (pinfunction "CATHODE_2") (pintype "bidirectional"))
      (node (ref "D9") (pin "2") (pinfunction "CATHODE_2") (pintype "bidirectional"))
      (node (ref "IC3") (pin "15") (pinfunction "O4_15") (pintype "open_collector"))
    )
    (net (code "60") (name "K_4") (class "Default")
      (node (ref "D10") (pin "2") (pinfunction "CATHODE_2") (pintype "bidirectional"))
      (node (ref "D11") (pin "2") (pinfunction "CATHODE_2") (pintype "bidirectional"))
      (node (ref "IC3") (pin "14") (pinfunction "O5_14") (pintype "open_collector"))
    )
    (net (code "61") (name "K_5") (class "Default")
      (node (ref "D12") (pin "2") (pinfunction "CATHODE_2") (pintype "bidirectional"))
      (node (ref "D13") (pin "2") (pinfunction "CATHODE_2") (pintype "bidirectional"))
      (node (ref "IC3") (pin "13") (pinfunction "O6_13") (pintype "open_collector"))
    )
    (net (code "62") (name "K_6") (class "Default")
      (node (ref "D14") (pin "2") (pinfunction "CATHODE_2") (pintype "bidirectional"))
      (node (ref "D15") (pin "2") (pinfunction "CATHODE_2") (pintype "bidirectional"))
      (node (ref "IC3") (pin "12") (pinfunction "O7_12") (pintype "open_collector"))
    )
    (net (code "63") (name "K_7") (class "Default")
      (node (ref "D16") (pin "2") (pinfunction "CATHODE_2") (pintype "bidirectional"))
      (node (ref "D17") (pin "2") (pinfunction "CATHODE_2") (pintype "bidirectional"))
      (node (ref "IC3") (pin "11") (pinfunction "O8_11") (pintype "open_collector"))
    )
    (net (code "64") (name "MOTOR1_AUX") (class "Default")
      (node (ref "CN3") (pin "2") (pinfunction "A+_2") (pintype "bidirectional"))
      (node (ref "DIS1") (pin "25") (pinfunction "PE7_25") (pintype "bidirectional"))
      (node (ref "MOT_1") (pin "6") (pinfunction "S_6") (pintype "passive"))
    )
    (net (code "65") (name "MOTOR1_EN") (class "Default")
      (node (ref "CN3") (pin "3") (pinfunction "A-_3") (pintype "bidirectional"))
      (node (ref "DIS1") (pin "24") (pinfunction "PB2_24") (pintype "bidirectional"))
      (node (ref "MOT_1") (pin "2") (pinfunction "S_2") (pintype "passive"))
    )
    (net (code "66") (name "MOTOR2_AUX") (class "Default")
      (node (ref "CN4") (pin "2") (pinfunction "A+_2") (pintype "bidirectional"))
      (node (ref "DIS1") (pin "30") (pinfunction "PE12_30") (pintype "bidirectional"))
      (node (ref "MOT_2") (pin "6") (pinfunction "S_6") (pintype "passive"))
    )
    (net (code "67") (name "MOTOR2_EN") (class "Default")
      (node (ref "CN4") (pin "3") (pinfunction "A-_3") (pintype "bidirectional"))
      (node (ref "DIS1") (pin "31") (pinfunction "PE13_31") (pintype "bidirectional"))
      (node (ref "MOT_2") (pin "2") (pinfunction "S_2") (pintype "passive"))
    )
    (net (code "68") (name "MUX_A") (class "Default")
      (node (ref "DIS1") (pin "95") (pinfunction "PC8_95") (pintype "bidirectional"))
      (node (ref "IC1") (pin "10") (pinfunction "A_10") (pintype "input"))
      (node (ref "IC1B") (pin "10") (pinfunction "A_10") (pintype "input"))
      (node (ref "IC2") (pin "10") (pinfunction "A_10") (pintype "input"))
      (node (ref "IC2B") (pin "10") (pinfunction "A_10") (pintype "input"))
    )
    (net (code "69") (name "MUX_B") (class "Default")
      (node (ref "DIS1") (pin "96") (pinfunction "PC9_96") (pintype "bidirectional"))
      (node (ref "IC1") (pin "11") (pinfunction "B_11") (pintype "input"))
      (node (ref "IC1B") (pin "11") (pinfunction "B_11") (pintype "input"))
      (node (ref "IC2") (pin "11") (pinfunction "B_11") (pintype "input"))
      (node (ref "IC2B") (pin "11") (pinfunction "B_11") (pintype "input"))
    )
    (net (code "70") (name "MUX_C") (class "Default")
      (node (ref "DIS1") (pin "93") (pinfunction "PA8_93") (pintype "bidirectional"))
      (node (ref "IC1") (pin "14") (pinfunction "C_14") (pintype "input"))
      (node (ref "IC1B") (pin "14") (pinfunction "C_14") (pintype "input"))
      (node (ref "IC2") (pin "14") (pinfunction "C_14") (pintype "input"))
      (node (ref "IC2B") (pin "14") (pinfunction "C_14") (pintype "input"))
    )
    (net (code "71") (name "MUX_D") (class "Default")
      (node (ref "DIS1") (pin "94") (pinfunction "PA9_94") (pintype "bidirectional"))
      (node (ref "IC1") (pin "13") (pinfunction "D_13") (pintype "input"))
      (node (ref "IC1B") (pin "13") (pinfunction "D_13") (pintype "input"))
      (node (ref "IC2") (pin "13") (pinfunction "D_13") (pintype "input"))
      (node (ref "IC2B") (pin "13") (pinfunction "D_13") (pintype "input"))
    )
    (net (code "72") (name "MUX_INH") (class "Default")
      (node (ref "DIS1") (pin "91") (pinfunction "PA10_91") (pintype "bidirectional"))
      (node (ref "IC1") (pin "15") (pinfunction "INH_15") (pintype "input"))
      (node (ref "IC1B") (pin "15") (pinfunction "INH_15") (pintype "input"))
      (node (ref "IC2") (pin "15") (pinfunction "INH_15") (pintype "input"))
      (node (ref "IC2B") (pin "15") (pinfunction "INH_15") (pintype "input"))
    )
    (net (code "73") (name "Net-(C1-Pad+)") (class "Default")
      (node (ref "C1") (pin "+") (pinfunction "+_+") (pintype "passive"))
      (node (ref "D1") (pin "C") (pinfunction "C_C") (pintype "passive"))
      (node (ref "JP1") (pin "1") (pinfunction "1_1") (pintype "passive"))
      (node (ref "U1") (pin "IN") (pinfunction "IN_IN") (pintype "input"))
    )
    (net (code "74") (name "Net-(CN1B-S)") (class "Default")
      (node (ref "CN1") (pin "2") (pinfunction "S_2") (pintype "passive"))
      (node (ref "D1") (pin "A") (pinfunction "A_A") (pintype "passive"))
    )
    (net (code "75") (name "Net-(CN2B-S)") (class "Default")
      (node (ref "C30") (pin "+") (pinfunction "+_+") (pintype "passive"))
      (node (ref "CN2") (pin "2") (pinfunction "S_2") (pintype "passive"))
      (node (ref "JP3") (pin "2") (pinfunction "2_2") (pintype "passive"))
      (node (ref "L1") (pin "1") (pinfunction "1_1") (pintype "passive"))
    )
    (net (code "76") (name "Net-(D2-BLUE_CATHODE)") (class "Default")
      (node (ref "D2") (pin "4") (pinfunction "BLUE_CATHODE_4") (pintype "bidirectional"))
      (node (ref "R5") (pin "1") (pinfunction "1_1") (pintype "passive"))
    )
    (net (code "77") (name "Net-(D2-GREEN_CATHODE)") (class "Default")
      (node (ref "D2") (pin "3") (pinfunction "GREEN_CATHODE_3") (pintype "bidirectional"))
      (node (ref "R7") (pin "1") (pinfunction "1_1") (pintype "passive"))
    )
    (net (code "78") (name "Net-(D2-RED_CATHODE)") (class "Default")
      (node (ref "D2") (pin "1") (pinfunction "RED_CATHODE_1") (pintype "bidirectional"))
      (node (ref "R9") (pin "1") (pinfunction "1_1") (pintype "passive"))
    )
    (net (code "79") (name "Net-(D3-BLUE_CATHODE)") (class "Default")
      (node (ref "D3") (pin "4") (pinfunction "BLUE_CATHODE_4") (pintype "bidirectional"))
      (node (ref "R6") (pin "1") (pinfunction "1_1") (pintype "passive"))
    )
    (net (code "80") (name "Net-(D3-GREEN_CATHODE)") (class "Default")
      (node (ref "D3") (pin "3") (pinfunction "GREEN_CATHODE_3") (pintype "bidirectional"))
      (node (ref "R8") (pin "1") (pinfunction "1_1") (pintype "passive"))
    )
    (net (code "81") (name "Net-(D3-RED_CATHODE)") (class "Default")
      (node (ref "D3") (pin "1") (pinfunction "RED_CATHODE_1") (pintype "bidirectional"))
      (node (ref "R10") (pin "1") (pinfunction "1_1") (pintype "passive"))
    )
    (net (code "82") (name "Net-(D4-BLUE_CATHODE)") (class "Default")
      (node (ref "D4") (pin "4") (pinfunction "BLUE_CATHODE_4") (pintype "bidirectional"))
      (node (ref "R11") (pin "1") (pinfunction "1_1") (pintype "passive"))
    )
    (net (code "83") (name "Net-(D4-GREEN_CATHODE)") (class "Default")
      (node (ref "D4") (pin "3") (pinfunction "GREEN_CATHODE_3") (pintype "bidirectional"))
      (node (ref "R13") (pin "1") (pinfunction "1_1") (pintype "passive"))
    )
    (net (code "84") (name "Net-(D4-RED_CATHODE)") (class "Default")
      (node (ref "D4") (pin "1") (pinfunction "RED_CATHODE_1") (pintype "bidirectional"))
      (node (ref "R17") (pin "1") (pinfunction "1_1") (pintype "passive"))
    )
    (net (code "85") (name "Net-(D5-BLUE_CATHODE)") (class "Default")
      (node (ref "D5") (pin "4") (pinfunction "BLUE_CATHODE_4") (pintype "bidirectional"))
      (node (ref "R12") (pin "1") (pinfunction "1_1") (pintype "passive"))
    )
    (net (code "86") (name "Net-(D5-GREEN_CATHODE)") (class "Default")
      (node (ref "D5") (pin "3") (pinfunction "GREEN_CATHODE_3") (pintype "bidirectional"))
      (node (ref "R16") (pin "1") (pinfunction "1_1") (pintype "passive"))
    )
    (net (code "87") (name "Net-(D5-RED_CATHODE)") (class "Default")
      (node (ref "D5") (pin "1") (pinfunction "RED_CATHODE_1") (pintype "bidirectional"))
      (node (ref "R18") (pin "1") (pinfunction "1_1") (pintype "passive"))
    )
    (net (code "88") (name "Net-(D6-BLUE_CATHODE)") (class "Default")
      (node (ref "D6") (pin "4") (pinfunction "BLUE_CATHODE_4") (pintype "bidirectional"))
      (node (ref "R19") (pin "1") (pinfunction "1_1") (pintype "passive"))
    )
    (net (code "89") (name "Net-(D6-GREEN_CATHODE)") (class "Default")
      (node (ref "D6") (pin "3") (pinfunction "GREEN_CATHODE_3") (pintype "bidirectional"))
      (node (ref "R21") (pin "1") (pinfunction "1_1") (pintype "passive"))
    )
    (net (code "90") (name "Net-(D6-RED_CATHODE)") (class "Default")
      (node (ref "D6") (pin "1") (pinfunction "RED_CATHODE_1") (pintype "bidirectional"))
      (node (ref "R23") (pin "1") (pinfunction "1_1") (pintype "passive"))
    )
    (net (code "91") (name "Net-(D7-BLUE_CATHODE)") (class "Default")
      (node (ref "D7") (pin "4") (pinfunction "BLUE_CATHODE_4") (pintype "bidirectional"))
      (node (ref "R20") (pin "1") (pinfunction "1_1") (pintype "passive"))
    )
    (net (code "92") (name "Net-(D7-GREEN_CATHODE)") (class "Default")
      (node (ref "D7") (pin "3") (pinfunction "GREEN_CATHODE_3") (pintype "bidirectional"))
      (node (ref "R22") (pin "1") (pinfunction "1_1") (pintype "passive"))
    )
    (net (code "93") (name "Net-(D7-RED_CATHODE)") (class "Default")
      (node (ref "D7") (pin "1") (pinfunction "RED_CATHODE_1") (pintype "bidirectional"))
      (node (ref "R24") (pin "1") (pinfunction "1_1") (pintype "passive"))
    )
    (net (code "94") (name "Net-(D8-BLUE_CATHODE)") (class "Default")
      (node (ref "D8") (pin "4") (pinfunction "BLUE_CATHODE_4") (pintype "bidirectional"))
      (node (ref "R25") (pin "1") (pinfunction "1_1") (pintype "passive"))
    )
    (net (code "95") (name "Net-(D8-GREEN_CATHODE)") (class "Default")
      (node (ref "D8") (pin "3") (pinfunction "GREEN_CATHODE_3") (pintype "bidirectional"))
      (node (ref "R27") (pin "1") (pinfunction "1_1") (pintype "passive"))
    )
    (net (code "96") (name "Net-(D8-RED_CATHODE)") (class "Default")
      (node (ref "D8") (pin "1") (pinfunction "RED_CATHODE_1") (pintype "bidirectional"))
      (node (ref "R29") (pin "1") (pinfunction "1_1") (pintype "passive"))
    )
    (net (code "97") (name "Net-(D9-BLUE_CATHODE)") (class "Default")
      (node (ref "D9") (pin "4") (pinfunction "BLUE_CATHODE_4") (pintype "bidirectional"))
      (node (ref "R26") (pin "1") (pinfunction "1_1") (pintype "passive"))
    )
    (net (code "98") (name "Net-(D9-GREEN_CATHODE)") (class "Default")
      (node (ref "D9") (pin "3") (pinfunction "GREEN_CATHODE_3") (pintype "bidirectional"))
      (node (ref "R28") (pin "1") (pinfunction "1_1") (pintype "passive"))
    )
    (net (code "99") (name "Net-(D9-RED_CATHODE)") (class "Default")
      (node (ref "D9") (pin "1") (pinfunction "RED_CATHODE_1") (pintype "bidirectional"))
      (node (ref "R30") (pin "1") (pinfunction "1_1") (pintype "passive"))
    )
    (net (code "100") (name "Net-(D10-BLUE_CATHODE)") (class "Default")
      (node (ref "D10") (pin "4") (pinfunction "BLUE_CATHODE_4") (pintype "bidirectional"))
      (node (ref "R32") (pin "1") (pinfunction "1_1") (pintype "passive"))
    )
    (net (code "101") (name "Net-(D10-GREEN_CATHODE)") (class "Default")
      (node (ref "D10") (pin "3") (pinfunction "GREEN_CATHODE_3") (pintype "bidirectional"))
      (node (ref "R35") (pin "1") (pinfunction "1_1") (pintype "passive"))
    )
    (net (code "102") (name "Net-(D10-RED_CATHODE)") (class "Default")
      (node (ref "D10") (pin "1") (pinfunction "RED_CATHODE_1") (pintype "bidirectional"))
      (node (ref "R37") (pin "1") (pinfunction "1_1") (pintype "passive"))
    )
    (net (code "103") (name "Net-(D11-BLUE_CATHODE)") (class "Default")
      (node (ref "D11") (pin "4") (pinfunction "BLUE_CATHODE_4") (pintype "bidirectional"))
      (node (ref "R34") (pin "1") (pinfunction "1_1") (pintype "passive"))
    )
    (net (code "104") (name "Net-(D11-GREEN_CATHODE)") (class "Default")
      (node (ref "D11") (pin "3") (pinfunction "GREEN_CATHODE_3") (pintype "bidirectional"))
      (node (ref "R36") (pin "1") (pinfunction "1_1") (pintype "passive"))
    )
    (net (code "105") (name "Net-(D11-RED_CATHODE)") (class "Default")
      (node (ref "D11") (pin "1") (pinfunction "RED_CATHODE_1") (pintype "bidirectional"))
      (node (ref "R38") (pin "1") (pinfunction "1_1") (pintype "passive"))
    )
    (net (code "106") (name "Net-(D12-BLUE_CATHODE)") (class "Default")
      (node (ref "D12") (pin "4") (pinfunction "BLUE_CATHODE_4") (pintype "bidirectional"))
      (node (ref "R39") (pin "1") (pinfunction "1_1") (pintype "passive"))
    )
    (net (code "107") (name "Net-(D12-GREEN_CATHODE)") (class "Default")
      (node (ref "D12") (pin "3") (pinfunction "GREEN_CATHODE_3") (pintype "bidirectional"))
      (node (ref "R41") (pin "1") (pinfunction "1_1") (pintype "passive"))
    )
    (net (code "108") (name "Net-(D12-RED_CATHODE)") (class "Default")
      (node (ref "D12") (pin "1") (pinfunction "RED_CATHODE_1") (pintype "bidirectional"))
      (node (ref "R43") (pin "1") (pinfunction "1_1") (pintype "passive"))
    )
    (net (code "109") (name "Net-(D13-BLUE_CATHODE)") (class "Default")
      (node (ref "D13") (pin "4") (pinfunction "BLUE_CATHODE_4") (pintype "bidirectional"))
      (node (ref "R40") (pin "1") (pinfunction "1_1") (pintype "passive"))
    )
    (net (code "110") (name "Net-(D13-GREEN_CATHODE)") (class "Default")
      (node (ref "D13") (pin "3") (pinfunction "GREEN_CATHODE_3") (pintype "bidirectional"))
      (node (ref "R42") (pin "1") (pinfunction "1_1") (pintype "passive"))
    )
    (net (code "111") (name "Net-(D13-RED_CATHODE)") (class "Default")
      (node (ref "D13") (pin "1") (pinfunction "RED_CATHODE_1") (pintype "bidirectional"))
      (node (ref "R44") (pin "1") (pinfunction "1_1") (pintype "passive"))
    )
    (net (code "112") (name "Net-(D14-BLUE_CATHODE)") (class "Default")
      (node (ref "D14") (pin "4") (pinfunction "BLUE_CATHODE_4") (pintype "bidirectional"))
      (node (ref "R45") (pin "1") (pinfunction "1_1") (pintype "passive"))
    )
    (net (code "113") (name "Net-(D14-GREEN_CATHODE)") (class "Default")
      (node (ref "D14") (pin "3") (pinfunction "GREEN_CATHODE_3") (pintype "bidirectional"))
      (node (ref "R47") (pin "1") (pinfunction "1_1") (pintype "passive"))
    )
    (net (code "114") (name "Net-(D14-RED_CATHODE)") (class "Default")
      (node (ref "D14") (pin "1") (pinfunction "RED_CATHODE_1") (pintype "bidirectional"))
      (node (ref "R49") (pin "1") (pinfunction "1_1") (pintype "passive"))
    )
    (net (code "115") (name "Net-(D15-BLUE_CATHODE)") (class "Default")
      (node (ref "D15") (pin "4") (pinfunction "BLUE_CATHODE_4") (pintype "bidirectional"))
      (node (ref "R46") (pin "1") (pinfunction "1_1") (pintype "passive"))
    )
    (net (code "116") (name "Net-(D15-GREEN_CATHODE)") (class "Default")
      (node (ref "D15") (pin "3") (pinfunction "GREEN_CATHODE_3") (pintype "bidirectional"))
      (node (ref "R48") (pin "1") (pinfunction "1_1") (pintype "passive"))
    )
    (net (code "117") (name "Net-(D15-RED_CATHODE)") (class "Default")
      (node (ref "D15") (pin "1") (pinfunction "RED_CATHODE_1") (pintype "bidirectional"))
      (node (ref "R50") (pin "1") (pinfunction "1_1") (pintype "passive"))
    )
    (net (code "118") (name "Net-(D16-BLUE_CATHODE)") (class "Default")
      (node (ref "D16") (pin "4") (pinfunction "BLUE_CATHODE_4") (pintype "bidirectional"))
      (node (ref "R51") (pin "1") (pinfunction "1_1") (pintype "passive"))
    )
    (net (code "119") (name "Net-(D16-GREEN_CATHODE)") (class "Default")
      (node (ref "D16") (pin "3") (pinfunction "GREEN_CATHODE_3") (pintype "bidirectional"))
      (node (ref "R53") (pin "1") (pinfunction "1_1") (pintype "passive"))
    )
    (net (code "120") (name "Net-(D16-RED_CATHODE)") (class "Default")
      (node (ref "D16") (pin "1") (pinfunction "RED_CATHODE_1") (pintype "bidirectional"))
      (node (ref "R55") (pin "1") (pinfunction "1_1") (pintype "passive"))
    )
    (net (code "121") (name "Net-(D17-BLUE_CATHODE)") (class "Default")
      (node (ref "D17") (pin "4") (pinfunction "BLUE_CATHODE_4") (pintype "bidirectional"))
      (node (ref "R52") (pin "1") (pinfunction "1_1") (pintype "passive"))
    )
    (net (code "122") (name "Net-(D17-GREEN_CATHODE)") (class "Default")
      (node (ref "D17") (pin "3") (pinfunction "GREEN_CATHODE_3") (pintype "bidirectional"))
      (node (ref "R54") (pin "1") (pinfunction "1_1") (pintype "passive"))
    )
    (net (code "123") (name "Net-(D17-RED_CATHODE)") (class "Default")
      (node (ref "D17") (pin "1") (pinfunction "RED_CATHODE_1") (pintype "bidirectional"))
      (node (ref "R56") (pin "1") (pinfunction "1_1") (pintype "passive"))
    )
    (net (code "124") (name "Net-(IC4A-C1+)") (class "Default")
      (node (ref "C34") (pin "+") (pinfunction "+_+") (pintype "passive"))
      (node (ref "IC4") (pin "1") (pinfunction "C1+_1") (pintype "bidirectional"))
    )
    (net (code "125") (name "Net-(IC4A-C1-)") (class "Default")
      (node (ref "C34") (pin "-") (pinfunction "-_-") (pintype "passive"))
      (node (ref "IC4") (pin "3") (pinfunction "C1-_3") (pintype "bidirectional"))
    )
    (net (code "126") (name "Net-(IC4A-C2+)") (class "Default")
      (node (ref "C35") (pin "+") (pinfunction "+_+") (pintype "passive"))
      (node (ref "IC4") (pin "4") (pinfunction "C2+_4") (pintype "bidirectional"))
    )
    (net (code "127") (name "Net-(IC4A-C2-)") (class "Default")
      (node (ref "C35") (pin "-") (pinfunction "-_-") (pintype "passive"))
      (node (ref "IC4") (pin "5") (pinfunction "C2-_5") (pintype "bidirectional"))
    )
    (net (code "128") (name "Net-(IC4A-R1OUT)") (class "Default")
      (node (ref "IC4") (pin "12") (pinfunction "R1OUT_12") (pintype "output"))
      (node (ref "JP8") (pin "1") (pinfunction "1_1") (pintype "passive"))
    )
    (net (code "129") (name "Net-(IC4A-T1IN)") (class "Default")
      (node (ref "IC4") (pin "11") (pinfunction "T1IN_11") (pintype "input"))
      (node (ref "JP8") (pin "3") (pinfunction "3_3") (pintype "passive"))
    )
    (net (code "130") (name "Net-(IC4A-V+)") (class "Default")
      (node (ref "C37") (pin "+") (pinfunction "+_+") (pintype "passive"))
      (node (ref "IC4") (pin "2") (pinfunction "V+_2") (pintype "bidirectional"))
    )
    (net (code "131") (name "Net-(IC4A-V-)") (class "Default")
      (node (ref "C38") (pin "-") (pinfunction "-_-") (pintype "passive"))
      (node (ref "IC4") (pin "6") (pinfunction "V-_6") (pintype "bidirectional"))
    )
    (net (code "132") (name "Net-(J1A-S)") (class "Default")
      (node (ref "C32") (pin "1") (pinfunction "1_1") (pintype "passive"))
      (node (ref "J1") (pin "1") (pinfunction "S_1") (pintype "passive"))
      (node (ref "R77") (pin "2") (pinfunction "2_2") (pintype "passive"))
      (node (ref "R78") (pin "2") (pinfunction "2_2") (pintype "passive"))
    )
    (net (code "133") (name "Net-(J2A-S)") (class "Default")
      (node (ref "C33") (pin "1") (pinfunction "1_1") (pintype "passive"))
      (node (ref "J2") (pin "1") (pinfunction "S_1") (pintype "passive"))
      (node (ref "R75") (pin "2") (pinfunction "2_2") (pintype "passive"))
      (node (ref "R76") (pin "2") (pinfunction "2_2") (pintype "passive"))
    )
    (net (code "134") (name "Net-(JP2-Pad1)") (class "Default")
      (node (ref "JP2") (pin "1") (pinfunction "1_1") (pintype "passive"))
      (node (ref "R2") (pin "2") (pinfunction "2_2") (pintype "passive"))
    )
    (net (code "135") (name "Net-(JP2-Pad6)") (class "Default")
      (node (ref "JP2") (pin "6") (pinfunction "6_6") (pintype "passive"))
      (node (ref "R1") (pin "2") (pinfunction "2_2") (pintype "passive"))
    )
    (net (code "136") (name "Net-(JP4-Pad1)") (class "Default")
      (node (ref "JP4") (pin "1") (pinfunction "1_1") (pintype "passive"))
      (node (ref "R57") (pin "2") (pinfunction "2_2") (pintype "passive"))
    )
    (net (code "137") (name "Net-(JP4-Pad3)") (class "Default")
      (node (ref "JP4") (pin "3") (pinfunction "3_3") (pintype "passive"))
      (node (ref "R58") (pin "2") (pinfunction "2_2") (pintype "passive"))
    )
    (net (code "138") (name "Net-(JP4-Pad5)") (class "Default")
      (node (ref "JP4") (pin "5") (pinfunction "5_5") (pintype "passive"))
      (node (ref "R59") (pin "2") (pinfunction "2_2") (pintype "passive"))
    )
    (net (code "139") (name "Net-(JP5-Pad2)") (class "Default")
      (node (ref "JP5") (pin "2") (pinfunction "2_2") (pintype "passive"))
      (node (ref "R63") (pin "1") (pinfunction "1_1") (pintype "passive"))
    )
    (net (code "140") (name "Net-(JP5-Pad4)") (class "Default")
      (node (ref "JP5") (pin "4") (pinfunction "4_4") (pintype "passive"))
      (node (ref "R64") (pin "1") (pinfunction "1_1") (pintype "passive"))
    )
    (net (code "141") (name "Net-(JP5-Pad6)") (class "Default")
      (node (ref "JP5") (pin "6") (pinfunction "6_6") (pintype "passive"))
      (node (ref "R65") (pin "1") (pinfunction "1_1") (pintype "passive"))
    )
    (net (code "142") (name "Net-(JP6-Pad1)") (class "Default")
      (node (ref "JP6") (pin "1") (pinfunction "1_1") (pintype "passive"))
      (node (ref "R66") (pin "2") (pinfunction "2_2") (pintype "passive"))
    )
    (net (code "143") (name "Net-(JP6-Pad3)") (class "Default")
      (node (ref "JP6") (pin "3") (pinfunction "3_3") (pintype "passive"))
      (node (ref "R67") (pin "2") (pinfunction "2_2") (pintype "passive"))
    )
    (net (code "144") (name "Net-(JP6-Pad5)") (class "Default")
      (node (ref "JP6") (pin "5") (pinfunction "5_5") (pintype "passive"))
      (node (ref "R68") (pin "2") (pinfunction "2_2") (pintype "passive"))
    )
    (net (code "145") (name "Net-(JP7-Pad2)") (class "Default")
      (node (ref "JP7") (pin "2") (pinfunction "2_2") (pintype "passive"))
      (node (ref "R72") (pin "1") (pinfunction "1_1") (pintype "passive"))
    )
    (net (code "146") (name "Net-(JP7-Pad4)") (class "Default")
      (node (ref "JP7") (pin "4") (pinfunction "4_4") (pintype "passive"))
      (node (ref "R73") (pin "1") (pinfunction "1_1") (pintype "passive"))
    )
    (net (code "147") (name "Net-(JP7-Pad6)") (class "Default")
      (node (ref "JP7") (pin "6") (pinfunction "6_6") (pintype "passive"))
      (node (ref "R74") (pin "1") (pinfunction "1_1") (pintype "passive"))
    )
    (net (code "148") (name "Net-(JP11-Pad1)") (class "Default")
      (node (ref "JP11") (pin "1") (pinfunction "1_1") (pintype "passive"))
      (node (ref "R83") (pin "2") (pinfunction "2_2") (pintype "passive"))
    )
    (net (code "149") (name "Net-(JP11-Pad3)") (class "Default")
      (node (ref "JP11") (pin "3") (pinfunction "3_3") (pintype "passive"))
      (node (ref "R84") (pin "1") (pinfunction "1_1") (pintype "passive"))
    )
    (net (code "150") (name "Net-(JP11-Pad5)") (class "Default")
      (node (ref "JP11") (pin "5") (pinfunction "5_5") (pintype "passive"))
      (node (ref "R85") (pin "2") (pinfunction "2_2") (pintype "passive"))
    )
    (net (code "151") (name "Net-(LED1-PadA)") (class "Default")
      (node (ref "LED1") (pin "A") (pinfunction "A_A") (pintype "passive"))
      (node (ref "R81") (pin "2") (pinfunction "2_2") (pintype "passive"))
    )
    (net (code "152") (name "Net-(LED2-PadA)") (class "Default")
      (node (ref "LED2") (pin "A") (pinfunction "A_A") (pintype "passive"))
      (node (ref "R82") (pin "1") (pinfunction "1_1") (pintype "passive"))
    )
    (net (code "153") (name "Net-(Q1-PadB)") (class "Default")
      (node (ref "Q1") (pin "B") (pinfunction "B_B") (pintype "passive"))
      (node (ref "R3") (pin "1") (pinfunction "1_1") (pintype "passive"))
    )
    (net (code "154") (name "Net-(Q1-PadC)") (class "Default")
      (node (ref "Q1") (pin "C") (pinfunction "C_C") (pintype "passive"))
      (node (ref "R11") (pin "2") (pinfunction "2_2") (pintype "passive"))
      (node (ref "R19") (pin "2") (pinfunction "2_2") (pintype "passive"))
      (node (ref "R25") (pin "2") (pinfunction "2_2") (pintype "passive"))
      (node (ref "R32") (pin "2") (pinfunction "2_2") (pintype "passive"))
      (node (ref "R39") (pin "2") (pinfunction "2_2") (pintype "passive"))
      (node (ref "R45") (pin "2") (pinfunction "2_2") (pintype "passive"))
      (node (ref "R5") (pin "2") (pinfunction "2_2") (pintype "passive"))
      (node (ref "R51") (pin "2") (pinfunction "2_2") (pintype "passive"))
    )
    (net (code "155") (name "Net-(Q2-PadB)") (class "Default")
      (node (ref "Q2") (pin "B") (pinfunction "B_B") (pintype "passive"))
      (node (ref "R4") (pin "1") (pinfunction "1_1") (pintype "passive"))
    )
    (net (code "156") (name "Net-(Q2-PadC)") (class "Default")
      (node (ref "Q2") (pin "C") (pinfunction "C_C") (pintype "passive"))
      (node (ref "R12") (pin "2") (pinfunction "2_2") (pintype "passive"))
      (node (ref "R20") (pin "2") (pinfunction "2_2") (pintype "passive"))
      (node (ref "R26") (pin "2") (pinfunction "2_2") (pintype "passive"))
      (node (ref "R34") (pin "2") (pinfunction "2_2") (pintype "passive"))
      (node (ref "R40") (pin "2") (pinfunction "2_2") (pintype "passive"))
      (node (ref "R46") (pin "2") (pinfunction "2_2") (pintype "passive"))
      (node (ref "R52") (pin "2") (pinfunction "2_2") (pintype "passive"))
      (node (ref "R6") (pin "2") (pinfunction "2_2") (pintype "passive"))
    )
    (net (code "157") (name "Net-(Q3-PadB)") (class "Default")
      (node (ref "Q3") (pin "B") (pinfunction "B_B") (pintype "passive"))
      (node (ref "R14") (pin "1") (pinfunction "1_1") (pintype "passive"))
    )
    (net (code "158") (name "Net-(Q3-PadC)") (class "Default")
      (node (ref "Q3") (pin "C") (pinfunction "C_C") (pintype "passive"))
      (node (ref "R13") (pin "2") (pinfunction "2_2") (pintype "passive"))
      (node (ref "R21") (pin "2") (pinfunction "2_2") (pintype "passive"))
      (node (ref "R27") (pin "2") (pinfunction "2_2") (pintype "passive"))
      (node (ref "R35") (pin "2") (pinfunction "2_2") (pintype "passive"))
      (node (ref "R41") (pin "2") (pinfunction "2_2") (pintype "passive"))
      (node (ref "R47") (pin "2") (pinfunction "2_2") (pintype "passive"))
      (node (ref "R53") (pin "2") (pinfunction "2_2") (pintype "passive"))
      (node (ref "R7") (pin "2") (pinfunction "2_2") (pintype "passive"))
    )
    (net (code "159") (name "Net-(Q4-PadB)") (class "Default")
      (node (ref "Q4") (pin "B") (pinfunction "B_B") (pintype "passive"))
      (node (ref "R15") (pin "1") (pinfunction "1_1") (pintype "passive"))
    )
    (net (code "160") (name "Net-(Q4-PadC)") (class "Default")
      (node (ref "Q4") (pin "C") (pinfunction "C_C") (pintype "passive"))
      (node (ref "R16") (pin "2") (pinfunction "2_2") (pintype "passive"))
      (node (ref "R22") (pin "2") (pinfunction "2_2") (pintype "passive"))
      (node (ref "R28") (pin "2") (pinfunction "2_2") (pintype "passive"))
      (node (ref "R36") (pin "2") (pinfunction "2_2") (pintype "passive"))
      (node (ref "R42") (pin "2") (pinfunction "2_2") (pintype "passive"))
      (node (ref "R48") (pin "2") (pinfunction "2_2") (pintype "passive"))
      (node (ref "R54") (pin "2") (pinfunction "2_2") (pintype "passive"))
      (node (ref "R8") (pin "2") (pinfunction "2_2") (pintype "passive"))
    )
    (net (code "161") (name "Net-(Q5-PadB)") (class "Default")
      (node (ref "Q5") (pin "B") (pinfunction "B_B") (pintype "passive"))
      (node (ref "R31") (pin "1") (pinfunction "1_1") (pintype "passive"))
    )
    (net (code "162") (name "Net-(Q5-PadC)") (class "Default")
      (node (ref "Q5") (pin "C") (pinfunction "C_C") (pintype "passive"))
      (node (ref "R17") (pin "2") (pinfunction "2_2") (pintype "passive"))
      (node (ref "R23") (pin "2") (pinfunction "2_2") (pintype "passive"))
      (node (ref "R29") (pin "2") (pinfunction "2_2") (pintype "passive"))
      (node (ref "R37") (pin "2") (pinfunction "2_2") (pintype "passive"))
      (node (ref "R43") (pin "2") (pinfunction "2_2") (pintype "passive"))
      (node (ref "R49") (pin "2") (pinfunction "2_2") (pintype "passive"))
      (node (ref "R55") (pin "2") (pinfunction "2_2") (pintype "passive"))
      (node (ref "R9") (pin "2") (pinfunction "2_2") (pintype "passive"))
    )
    (net (code "163") (name "Net-(Q6-PadB)") (class "Default")
      (node (ref "Q6") (pin "B") (pinfunction "B_B") (pintype "passive"))
      (node (ref "R33") (pin "1") (pinfunction "1_1") (pintype "passive"))
    )
    (net (code "164") (name "Net-(Q6-PadC)") (class "Default")
      (node (ref "Q6") (pin "C") (pinfunction "C_C") (pintype "passive"))
      (node (ref "R10") (pin "2") (pinfunction "2_2") (pintype "passive"))
      (node (ref "R18") (pin "2") (pinfunction "2_2") (pintype "passive"))
      (node (ref "R24") (pin "2") (pinfunction "2_2") (pintype "passive"))
      (node (ref "R30") (pin "2") (pinfunction "2_2") (pintype "passive"))
      (node (ref "R38") (pin "2") (pinfunction "2_2") (pintype "passive"))
      (node (ref "R44") (pin "2") (pinfunction "2_2") (pintype "passive"))
      (node (ref "R50") (pin "2") (pinfunction "2_2") (pintype "passive"))
      (node (ref "R56") (pin "2") (pinfunction "2_2") (pintype "passive"))
    )
    (net (code "165") (name "Net-(R80-Pad1)") (class "Default")
      (node (ref "R80") (pin "1") (pinfunction "1_1") (pintype "passive"))
      (node (ref "X1") (pin "6") (pinfunction "6_6") (pintype "passive"))
    )
    (net (code "166") (name "Net-(R86-Pad2)") (class "Default")
      (node (ref "R86") (pin "2") (pinfunction "2_2") (pintype "passive"))
      (node (ref "X1") (pin "4") (pinfunction "4_4") (pintype "passive"))
    )
    (net (code "167") (name "Net-(U3-DE)") (class "Default")
      (node (ref "JP9") (pin "3") (pinfunction "3_3") (pintype "passive"))
      (node (ref "R79") (pin "2") (pinfunction "2_2") (pintype "passive"))
      (node (ref "U3") (pin "2") (pinfunction "RE/_2") (pintype "input"))
      (node (ref "U3") (pin "3") (pinfunction "DE_3") (pintype "input"))
    )
    (net (code "168") (name "Net-(U3-DI)") (class "Default")
      (node (ref "JP9") (pin "1") (pinfunction "1_1") (pintype "passive"))
      (node (ref "U3") (pin "4") (pinfunction "DI_4") (pintype "input"))
    )
    (net (code "169") (name "Net-(U3-RO)") (class "Default")
      (node (ref "JP9") (pin "5") (pinfunction "5_5") (pintype "passive"))
      (node (ref "U3") (pin "1") (pinfunction "RO_1") (pintype "output"))
    )
    (net (code "170") (name "Net-(XB1-ASSOC{slash}AD5{slash}DIO5)") (class "Default")
      (node (ref "R82") (pin "2") (pinfunction "2_2") (pintype "passive"))
      (node (ref "XB1") (pin "15") (pinfunction "ASSOC/AD5/DIO5_15") (pintype "bidirectional"))
    )
    (net (code "171") (name "Net-(XB1-PWM0{slash}RSSI)") (class "Default")
      (node (ref "R81") (pin "1") (pinfunction "1_1") (pintype "passive"))
      (node (ref "XB1") (pin "6") (pinfunction "PWM0/RSSI_6") (pintype "output"))
    )
    (net (code "172") (name "P1") (class "Default")
      (node (ref "DIS1") (pin "36") (pinfunction "PB12_36") (pintype "bidirectional"))
      (node (ref "P1") (pin "1") (pinfunction "P1_1") (pintype "passive"))
      (node (ref "P1") (pin "2") (pinfunction "P_2") (pintype "passive"))
      (node (ref "R87") (pin "2") (pinfunction "2_2") (pintype "passive"))
    )
    (net (code "173") (name "P2") (class "Default")
      (node (ref "DIS1") (pin "37") (pinfunction "PB13_37") (pintype "bidirectional"))
      (node (ref "P2") (pin "1") (pinfunction "P1_1") (pintype "passive"))
      (node (ref "P2") (pin "2") (pinfunction "P_2") (pintype "passive"))
      (node (ref "R88") (pin "2") (pinfunction "2_2") (pintype "passive"))
    )
    (net (code "174") (name "PWM_CH1_N") (class "Default")
      (node (ref "CN3") (pin "5") (pinfunction "B-_5") (pintype "bidirectional"))
      (node (ref "DIS1") (pin "26") (pinfunction "PE8_26") (pintype "bidirectional"))
      (node (ref "MOT_1") (pin "3") (pinfunction "S_3") (pintype "passive"))
    )
    (net (code "175") (name "PWM_CH1_P") (class "Default")
      (node (ref "CN3") (pin "6") (pinfunction "B+_6") (pintype "bidirectional"))
      (node (ref "DIS1") (pin "27") (pinfunction "PE9_27") (pintype "bidirectional"))
      (node (ref "MOT_1") (pin "4") (pinfunction "S_4") (pintype "passive"))
    )
    (net (code "176") (name "PWM_CH2_N") (class "Default")
      (node (ref "CN4") (pin "5") (pinfunction "B-_5") (pintype "bidirectional"))
      (node (ref "DIS1") (pin "28") (pinfunction "PE10_28") (pintype "bidirectional"))
      (node (ref "MOT_2") (pin "3") (pinfunction "S_3") (pintype "passive"))
    )
    (net (code "177") (name "PWM_CH2_P") (class "Default")
      (node (ref "CN4") (pin "6") (pinfunction "B+_6") (pintype "bidirectional"))
      (node (ref "DIS1") (pin "29") (pinfunction "PE11_29") (pintype "bidirectional"))
      (node (ref "MOT_2") (pin "4") (pinfunction "S_4") (pintype "passive"))
    )
    (net (code "178") (name "RXD") (class "Default")
      (node (ref "IC4") (pin "13") (pinfunction "R1IN_13") (pintype "input"))
      (node (ref "X1") (pin "3") (pinfunction "3_3") (pintype "passive"))
    )
    (net (code "179") (name "TRIGGER_MUX") (class "Default")
      (node (ref "DIS1") (pin "70") (pinfunction "PB9_70") (pintype "bidirectional"))
      (node (ref "IC1") (pin "1") (pinfunction "X_1") (pintype "output"))
      (node (ref "IC1B") (pin "1") (pinfunction "X_1") (pintype "output"))
    )
    (net (code "180") (name "TRIGGER_U1") (class "Default")
      (node (ref "IC1") (pin "9") (pinfunction "X0_9") (pintype "input"))
      (node (ref "IC1B") (pin "9") (pinfunction "X0_9") (pintype "input"))
      (node (ref "SN1") (pin "2") (pinfunction "S_2") (pintype "passive"))
    )
    (net (code "181") (name "TRIGGER_U2") (class "Default")
      (node (ref "IC1") (pin "8") (pinfunction "X1_8") (pintype "input"))
      (node (ref "IC1B") (pin "8") (pinfunction "X1_8") (pintype "input"))
      (node (ref "SN2") (pin "2") (pinfunction "S_2") (pintype "passive"))
    )
    (net (code "182") (name "TRIGGER_U3") (class "Default")
      (node (ref "IC1") (pin "7") (pinfunction "X2_7") (pintype "input"))
      (node (ref "IC1B") (pin "7") (pinfunction "X2_7") (pintype "input"))
      (node (ref "SN3") (pin "2") (pinfunction "S_2") (pintype "passive"))
    )
    (net (code "183") (name "TRIGGER_U4") (class "Default")
      (node (ref "IC1") (pin "6") (pinfunction "X3_6") (pintype "input"))
      (node (ref "IC1B") (pin "6") (pinfunction "X3_6") (pintype "input"))
      (node (ref "SN4") (pin "2") (pinfunction "S_2") (pintype "passive"))
    )
    (net (code "184") (name "TRIGGER_U5") (class "Default")
      (node (ref "IC1") (pin "5") (pinfunction "X4_5") (pintype "input"))
      (node (ref "IC1B") (pin "5") (pinfunction "X4_5") (pintype "input"))
      (node (ref "SN5") (pin "2") (pinfunction "S_2") (pintype "passive"))
    )
    (net (code "185") (name "TRIGGER_U6") (class "Default")
      (node (ref "IC1") (pin "4") (pinfunction "X5_4") (pintype "input"))
      (node (ref "IC1B") (pin "4") (pinfunction "X5_4") (pintype "input"))
      (node (ref "SN6") (pin "2") (pinfunction "S_2") (pintype "passive"))
    )
    (net (code "186") (name "TRIGGER_U7") (class "Default")
      (node (ref "IC1") (pin "3") (pinfunction "X6_3") (pintype "input"))
      (node (ref "IC1B") (pin "3") (pinfunction "X6_3") (pintype "input"))
      (node (ref "SN7") (pin "2") (pinfunction "S_2") (pintype "passive"))
    )
    (net (code "187") (name "TRIGGER_U8") (class "Default")
      (node (ref "IC1") (pin "2") (pinfunction "X7_2") (pintype "input"))
      (node (ref "IC1B") (pin "2") (pinfunction "X7_2") (pintype "input"))
      (node (ref "SN8") (pin "2") (pinfunction "S_2") (pintype "passive"))
    )
    (net (code "188") (name "TRIGGER_U9") (class "Default")
      (node (ref "IC1") (pin "23") (pinfunction "X8_23") (pintype "input"))
      (node (ref "IC1B") (pin "23") (pinfunction "X8_23") (pintype "input"))
      (node (ref "SN9") (pin "2") (pinfunction "S_2") (pintype "passive"))
    )
    (net (code "189") (name "TRIGGER_U10") (class "Default")
      (node (ref "IC1") (pin "22") (pinfunction "X9_22") (pintype "input"))
      (node (ref "IC1B") (pin "22") (pinfunction "X9_22") (pintype "input"))
      (node (ref "SN10") (pin "2") (pinfunction "S_2") (pintype "passive"))
    )
    (net (code "190") (name "TRIGGER_U11") (class "Default")
      (node (ref "IC1") (pin "21") (pinfunction "X10_21") (pintype "input"))
      (node (ref "IC1B") (pin "21") (pinfunction "X10_21") (pintype "input"))
      (node (ref "SN11") (pin "2") (pinfunction "S_2") (pintype "passive"))
    )
    (net (code "191") (name "TRIGGER_U12") (class "Default")
      (node (ref "IC1") (pin "20") (pinfunction "X11_20") (pintype "input"))
      (node (ref "IC1B") (pin "20") (pinfunction "X11_20") (pintype "input"))
      (node (ref "SN12") (pin "2") (pinfunction "S_2") (pintype "passive"))
    )
    (net (code "192") (name "TRIGGER_U13") (class "Default")
      (node (ref "IC1") (pin "19") (pinfunction "X12_19") (pintype "input"))
      (node (ref "IC1B") (pin "19") (pinfunction "X12_19") (pintype "input"))
      (node (ref "SN13") (pin "2") (pinfunction "S_2") (pintype "passive"))
    )
    (net (code "193") (name "TRIGGER_U14") (class "Default")
      (node (ref "IC1") (pin "18") (pinfunction "X13_18") (pintype "input"))
      (node (ref "IC1B") (pin "18") (pinfunction "X13_18") (pintype "input"))
      (node (ref "SN14") (pin "2") (pinfunction "S_2") (pintype "passive"))
    )
    (net (code "194") (name "TRIGGER_U15") (class "Default")
      (node (ref "IC1") (pin "17") (pinfunction "X14_17") (pintype "input"))
      (node (ref "IC1B") (pin "17") (pinfunction "X14_17") (pintype "input"))
      (node (ref "SN15") (pin "2") (pinfunction "S_2") (pintype "passive"))
    )
    (net (code "195") (name "TRIGGER_U16") (class "Default")
      (node (ref "IC1") (pin "16") (pinfunction "X15_16") (pintype "input"))
      (node (ref "IC1B") (pin "16") (pinfunction "X15_16") (pintype "input"))
      (node (ref "SN16") (pin "2") (pinfunction "S_2") (pintype "passive"))
    )
    (net (code "196") (name "TR_S1_BLUE") (class "Default")
      (node (ref "DIS1") (pin "84") (pinfunction "PD2_84") (pintype "bidirectional"))
      (node (ref "R3") (pin "2") (pinfunction "2_2") (pintype "passive"))
    )
    (net (code "197") (name "TR_S1_GREEN") (class "Default")
      (node (ref "DIS1") (pin "83") (pinfunction "PD1_83") (pintype "bidirectional"))
      (node (ref "R14") (pin "2") (pinfunction "2_2") (pintype "passive"))
    )
    (net (code "198") (name "TR_S1_RED") (class "Default")
      (node (ref "DIS1") (pin "86") (pinfunction "PD0_86") (pintype "bidirectional"))
      (node (ref "R31") (pin "2") (pinfunction "2_2") (pintype "passive"))
    )
    (net (code "199") (name "TR_S2_BLUE") (class "Default")
      (node (ref "DIS1") (pin "79") (pinfunction "PD5_79") (pintype "bidirectional"))
      (node (ref "R4") (pin "2") (pinfunction "2_2") (pintype "passive"))
    )
    (net (code "200") (name "TR_S2_GREEN") (class "Default")
      (node (ref "DIS1") (pin "82") (pinfunction "PD4_82") (pintype "bidirectional"))
      (node (ref "R15") (pin "2") (pinfunction "2_2") (pintype "passive"))
    )
    (net (code "201") (name "TR_S2_RED") (class "Default")
      (node (ref "DIS1") (pin "81") (pinfunction "PD3_81") (pintype "bidirectional"))
      (node (ref "R33") (pin "2") (pinfunction "2_2") (pintype "passive"))
    )
    (net (code "202") (name "TXD") (class "Default")
      (node (ref "IC4") (pin "14") (pinfunction "T1OUT_14") (pintype "output"))
      (node (ref "X1") (pin "2") (pinfunction "2_2") (pintype "passive"))
    )
    (net (code "203") (name "unconnected-(DIS1A-BOOT0-Pad71)") (class "Default")
      (node (ref "DIS1") (pin "71") (pinfunction "BOOT0_71") (pintype "bidirectional"))
    )
    (net (code "204") (name "unconnected-(DIS1A-NC-Pad48)") (class "Default")
      (node (ref "DIS1") (pin "48") (pinfunction "NC_48") (pintype "bidirectional"))
    )
    (net (code "205") (name "unconnected-(DIS1A-NRST-Pad6)") (class "Default")
      (node (ref "DIS1") (pin "6") (pinfunction "NRST_6") (pintype "bidirectional"))
    )
    (net (code "206") (name "unconnected-(DIS1A-PA0-Pad12)") (class "Default")
      (node (ref "DIS1") (pin "12") (pinfunction "PA0_12") (pintype "bidirectional"))
    )
    (net (code "207") (name "unconnected-(DIS1A-PA13-Pad92)") (class "Default")
      (node (ref "DIS1") (pin "92") (pinfunction "PA13_92") (pintype "bidirectional"))
    )
    (net (code "208") (name "unconnected-(DIS1A-PA14-Pad89)") (class "Default")
      (node (ref "DIS1") (pin "89") (pinfunction "PA14_89") (pintype "bidirectional"))
    )
    (net (code "209") (name "unconnected-(DIS1A-PA15-Pad90)") (class "Default")
      (node (ref "DIS1") (pin "90") (pinfunction "PA15_90") (pintype "bidirectional"))
    )
    (net (code "210") (name "unconnected-(DIS1A-PB0-Pad22)") (class "Default")
      (node (ref "DIS1") (pin "22") (pinfunction "PB0_22") (pintype "bidirectional"))
    )
    (net (code "211") (name "unconnected-(DIS1A-PB1-Pad21)") (class "Default")
      (node (ref "DIS1") (pin "21") (pinfunction "PB1_21") (pintype "bidirectional"))
    )
    (net (code "212") (name "unconnected-(DIS1A-PB3-Pad78)") (class "Default")
      (node (ref "DIS1") (pin "78") (pinfunction "PB3_78") (pintype "bidirectional"))
    )
    (net (code "213") (name "unconnected-(DIS1A-PB4-Pad75)") (class "Default")
      (node (ref "DIS1") (pin "75") (pinfunction "PB4_75") (pintype "bidirectional"))
    )
    (net (code "214") (name "unconnected-(DIS1A-PB8-Pad69)") (class "Default")
      (node (ref "DIS1") (pin "69") (pinfunction "PB8_69") (pintype "bidirectional"))
    )
    (net (code "215") (name "unconnected-(DIS1A-PB15-Pad39)") (class "Default")
      (node (ref "DIS1") (pin "39") (pinfunction "PB15_39") (pintype "bidirectional"))
    )
    (net (code "216") (name "unconnected-(DIS1A-PC0-Pad8)") (class "Default")
      (node (ref "DIS1") (pin "8") (pinfunction "PC0_8") (pintype "bidirectional"))
    )
    (net (code "217") (name "unconnected-(DIS1A-PC1-Pad7)") (class "Default")
      (node (ref "DIS1") (pin "7") (pinfunction "PC1_7") (pintype "bidirectional"))
    )
    (net (code "218") (name "unconnected-(DIS1A-PC2-Pad10)") (class "Default")
      (node (ref "DIS1") (pin "10") (pinfunction "PC2_10") (pintype "bidirectional"))
    )
    (net (code "219") (name "unconnected-(DIS1A-PC3-Pad9)") (class "Default")
      (node (ref "DIS1") (pin "9") (pinfunction "PC3_9") (pintype "bidirectional"))
    )
    (net (code "220") (name "unconnected-(DIS1A-PC6-Pad97)") (class "Default")
      (node (ref "DIS1") (pin "97") (pinfunction "PC6_97") (pintype "bidirectional"))
    )
    (net (code "221") (name "unconnected-(DIS1A-PC7-Pad98)") (class "Default")
      (node (ref "DIS1") (pin "98") (pinfunction "PC7_98") (pintype "bidirectional"))
    )
    (net (code "222") (name "unconnected-(DIS1A-PC10-Pad87)") (class "Default")
      (node (ref "DIS1") (pin "87") (pinfunction "PC10_87") (pintype "bidirectional"))
    )
    (net (code "223") (name "unconnected-(DIS1A-PC11-Pad88)") (class "Default")
      (node (ref "DIS1") (pin "88") (pinfunction "PC11_88") (pintype "bidirectional"))
    )
    (net (code "224") (name "unconnected-(DIS1A-PC12-Pad85)") (class "Default")
      (node (ref "DIS1") (pin "85") (pinfunction "PC12_85") (pintype "bidirectional"))
    )
    (net (code "225") (name "unconnected-(DIS1A-PC13-Pad62)") (class "Default")
      (node (ref "DIS1") (pin "62") (pinfunction "PC13_62") (pintype "bidirectional"))
    )
    (net (code "226") (name "unconnected-(DIS1A-PC14-Pad59)") (class "Default")
      (node (ref "DIS1") (pin "59") (pinfunction "PC14_59") (pintype "bidirectional"))
    )
    (net (code "227") (name "unconnected-(DIS1A-PC15-Pad60)") (class "Default")
      (node (ref "DIS1") (pin "60") (pinfunction "PC15_60") (pintype "bidirectional"))
    )
    (net (code "228") (name "unconnected-(DIS1A-PD14-Pad46)") (class "Default")
      (node (ref "DIS1") (pin "46") (pinfunction "PD14_46") (pintype "bidirectional"))
    )
    (net (code "229") (name "unconnected-(DIS1A-PD15-Pad47)") (class "Default")
      (node (ref "DIS1") (pin "47") (pinfunction "PD15_47") (pintype "bidirectional"))
    )
    (net (code "230") (name "unconnected-(DIS1A-PE0-Pad67)") (class "Default")
      (node (ref "DIS1") (pin "67") (pinfunction "PE0_67") (pintype "bidirectional"))
    )
    (net (code "231") (name "unconnected-(DIS1A-PE1-Pad68)") (class "Default")
      (node (ref "DIS1") (pin "68") (pinfunction "PE1_68") (pintype "bidirectional"))
    )
    (net (code "232") (name "unconnected-(DIS1A-PE2-Pad65)") (class "Default")
      (node (ref "DIS1") (pin "65") (pinfunction "PE2_65") (pintype "bidirectional"))
    )
    (net (code "233") (name "unconnected-(DIS1A-PE3-Pad66)") (class "Default")
      (node (ref "DIS1") (pin "66") (pinfunction "PE3_66") (pintype "bidirectional"))
    )
    (net (code "234") (name "unconnected-(DIS1A-PE4-Pad63)") (class "Default")
      (node (ref "DIS1") (pin "63") (pinfunction "PE4_63") (pintype "bidirectional"))
    )
    (net (code "235") (name "unconnected-(DIS1A-PE5-Pad64)") (class "Default")
      (node (ref "DIS1") (pin "64") (pinfunction "PE5_64") (pintype "bidirectional"))
    )
    (net (code "236") (name "unconnected-(DIS1A-PE6-Pad61)") (class "Default")
      (node (ref "DIS1") (pin "61") (pinfunction "PE6_61") (pintype "bidirectional"))
    )
    (net (code "237") (name "unconnected-(DIS1A-PH0-Pad57)") (class "Default")
      (node (ref "DIS1") (pin "57") (pinfunction "PH0_57") (pintype "bidirectional"))
    )
    (net (code "238") (name "unconnected-(DIS1A-PH1-Pad58)") (class "Default")
      (node (ref "DIS1") (pin "58") (pinfunction "PH1_58") (pintype "bidirectional"))
    )
    (net (code "239") (name "unconnected-(ENC_1E-S-Pad5)") (class "Default")
      (node (ref "ENC_1") (pin "5") (pinfunction "S_5") (pintype "passive"))
    )
    (net (code "240") (name "unconnected-(ENC_2E-S-Pad5)") (class "Default")
      (node (ref "ENC_2") (pin "5") (pinfunction "S_5") (pintype "passive"))
    )
    (net (code "241") (name "unconnected-(IC4A-R2IN-Pad8)") (class "Default")
      (node (ref "IC4") (pin "8") (pinfunction "R2IN_8") (pintype "input"))
    )
    (net (code "242") (name "unconnected-(IC4A-R2OUT-Pad9)") (class "Default")
      (node (ref "IC4") (pin "9") (pinfunction "R2OUT_9") (pintype "output"))
    )
    (net (code "243") (name "unconnected-(IC4A-T2IN-Pad10)") (class "Default")
      (node (ref "IC4") (pin "10") (pinfunction "T2IN_10") (pintype "input"))
    )
    (net (code "244") (name "unconnected-(IC4A-T2OUT-Pad7)") (class "Default")
      (node (ref "IC4") (pin "7") (pinfunction "T2OUT_7") (pintype "output"))
    )
    (net (code "245") (name "unconnected-(X1-Pad1)") (class "Default")
      (node (ref "X1") (pin "1") (pinfunction "1_1") (pintype "passive"))
    )
    (net (code "246") (name "unconnected-(X1-Pad7)") (class "Default")
      (node (ref "X1") (pin "7") (pinfunction "7_7") (pintype "passive"))
    )
    (net (code "247") (name "unconnected-(X1-Pad8)") (class "Default")
      (node (ref "X1") (pin "8") (pinfunction "8_8") (pintype "passive"))
    )
    (net (code "248") (name "unconnected-(X1-Pad9)") (class "Default")
      (node (ref "X1") (pin "9") (pinfunction "9_9") (pintype "passive"))
    )
    (net (code "249") (name "unconnected-(XB1-AD0{slash}DIO0-Pad20)") (class "Default")
      (node (ref "XB1") (pin "20") (pinfunction "AD0/DIO0_20") (pintype "bidirectional"))
    )
    (net (code "250") (name "unconnected-(XB1-AD1{slash}DIO1-Pad19)") (class "Default")
      (node (ref "XB1") (pin "19") (pinfunction "AD1/DIO1_19") (pintype "bidirectional"))
    )
    (net (code "251") (name "unconnected-(XB1-AD2{slash}DIO2-Pad18)") (class "Default")
      (node (ref "XB1") (pin "18") (pinfunction "AD2/DIO2_18") (pintype "bidirectional"))
    )
    (net (code "252") (name "unconnected-(XB1-CD{slash}DOUT_EN{slash}DO8-Pad4)") (class "Default")
      (node (ref "XB1") (pin "4") (pinfunction "CD/DOUT_EN/DO8_4") (pintype "output"))
    )
    (net (code "253") (name "unconnected-(XB1-COORD_SEL{slash}AD3{slash}DIO3-Pad17)") (class "Default")
      (node (ref "XB1") (pin "17") (pinfunction "COORD_SEL/AD3/DIO3_17") (pintype "bidirectional"))
    )
    (net (code "254") (name "unconnected-(XB1-ON{slash}~{SLEEP}-Pad13)") (class "Default")
      (node (ref "XB1") (pin "13") (pinfunction "ON/~{SLEEP}_13") (pintype "output"))
    )
    (net (code "255") (name "unconnected-(XB1-RF_TX{slash}AD4{slash}DIO4-Pad11)") (class "Default")
      (node (ref "XB1") (pin "11") (pinfunction "RF_TX/AD4/DIO4_11") (pintype "bidirectional"))
    )
    (net (code "256") (name "unconnected-(XB1-VREF-Pad14)") (class "Default")
      (node (ref "XB1") (pin "14") (pinfunction "VREF_14") (pintype "input"))
    )
    (net (code "257") (name "unconnected-(XB1-~{CTS}{slash}DIO7-Pad12)") (class "Default")
      (node (ref "XB1") (pin "12") (pinfunction "~{CTS}/DIO7_12") (pintype "bidirectional"))
    )
    (net (code "258") (name "unconnected-(XB1-~{DTR}{slash}SLEEP_RQ{slash}DI8-Pad9)") (class "Default")
      (node (ref "XB1") (pin "9") (pinfunction "~{DTR}/SLEEP_RQ/DI8_9") (pintype "bidirectional"))
    )
    (net (code "259") (name "unconnected-(XB1-~{RESET}-Pad5)") (class "Default")
      (node (ref "XB1") (pin "5") (pinfunction "~{RESET}_5") (pintype "input"))
    )
    (net (code "260") (name "unconnected-(XB1-~{RTS}{slash}AD6{slash}DIO6-Pad16)") (class "Default")
      (node (ref "XB1") (pin "16") (pinfunction "~{RTS}/AD6/DIO6_16") (pintype "bidirectional"))
    )
  )
)
